# PM_Controller_v1p01.net
KiCad netlist of a schematic drawn in EAGLE
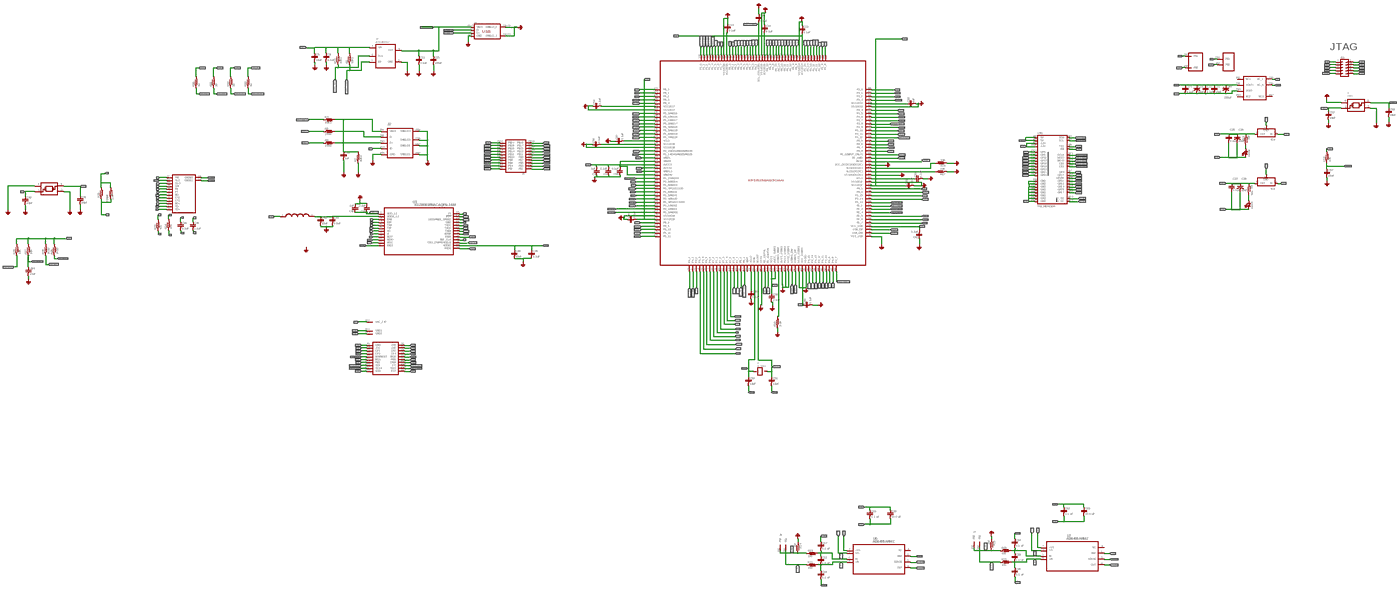
[diagram p0: schematic, sheet 1, overview]
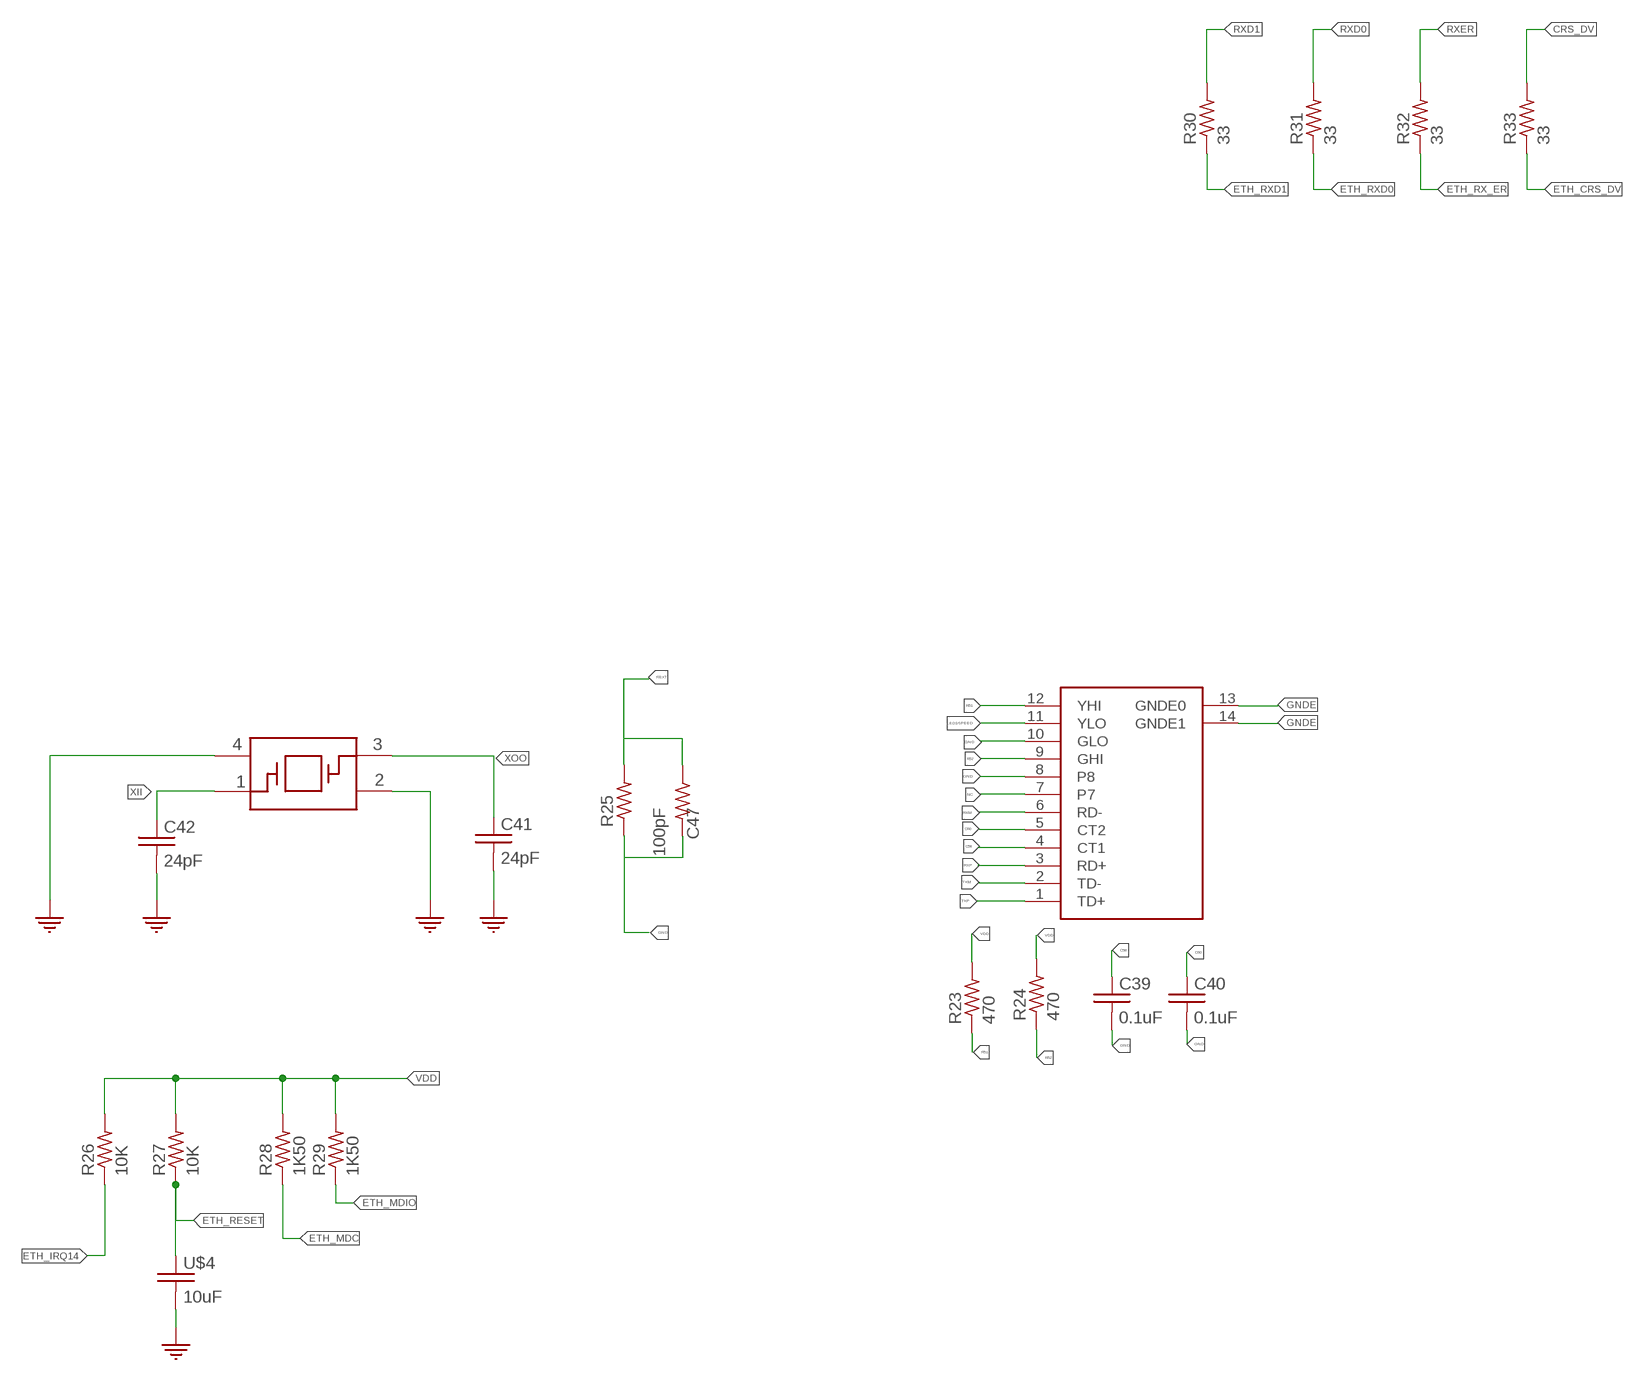
[diagram p1: schematic, sheet 1, part 1 of 6]
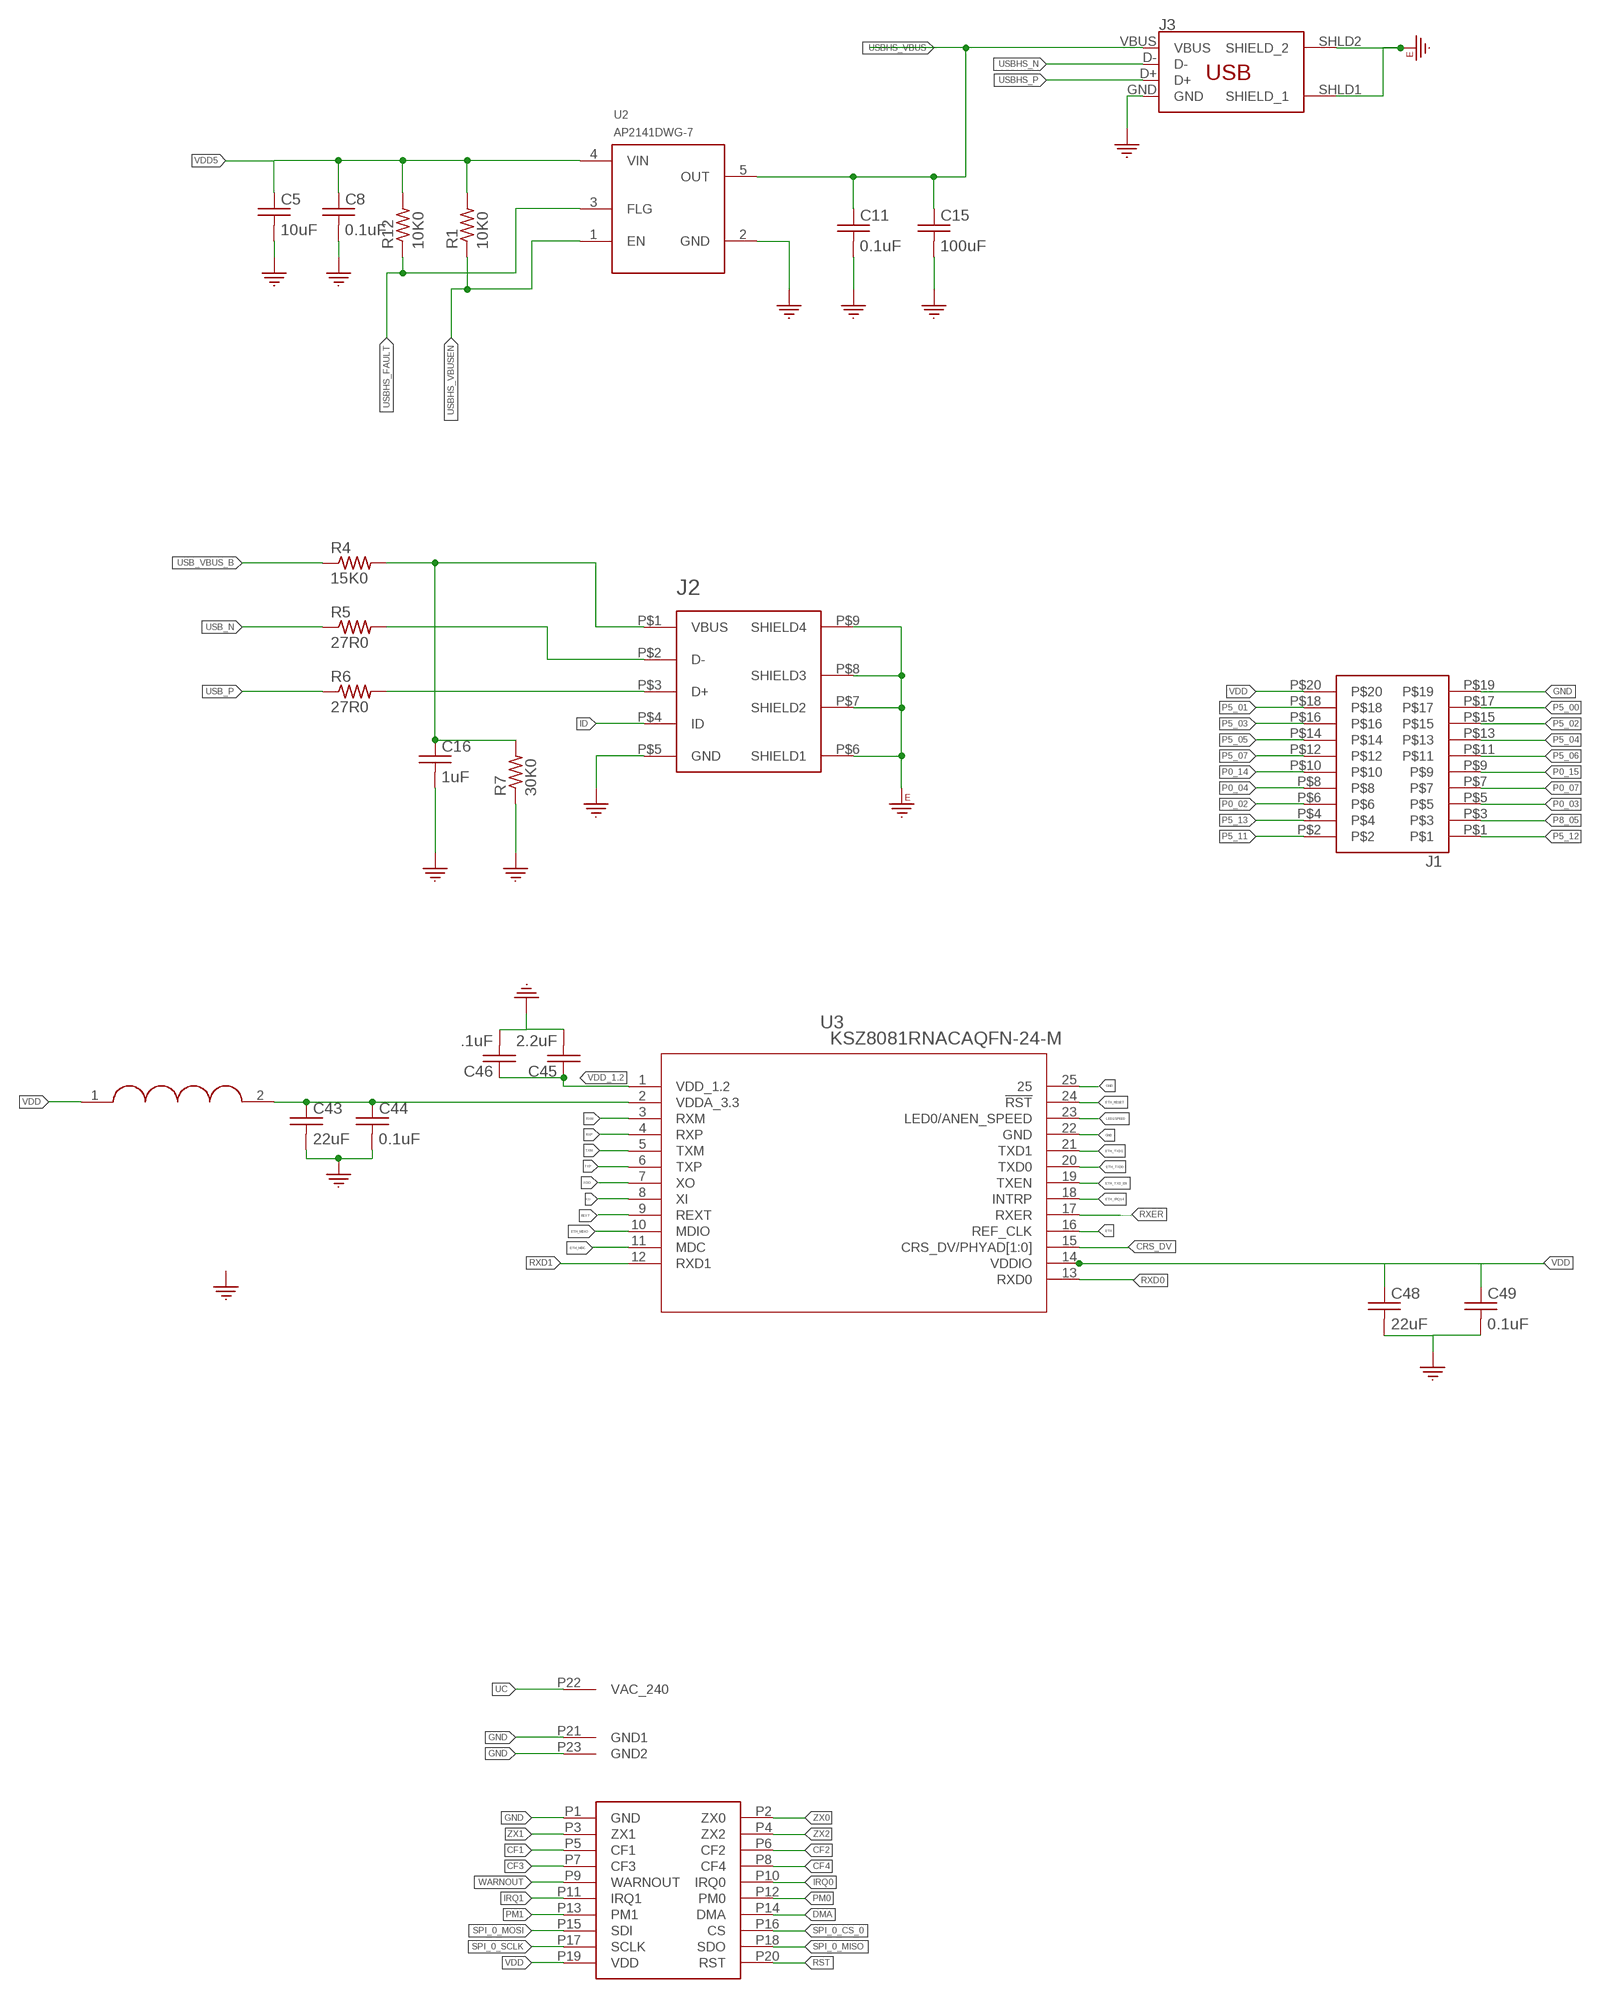
[diagram p2: schematic, sheet 1, part 2 of 6]
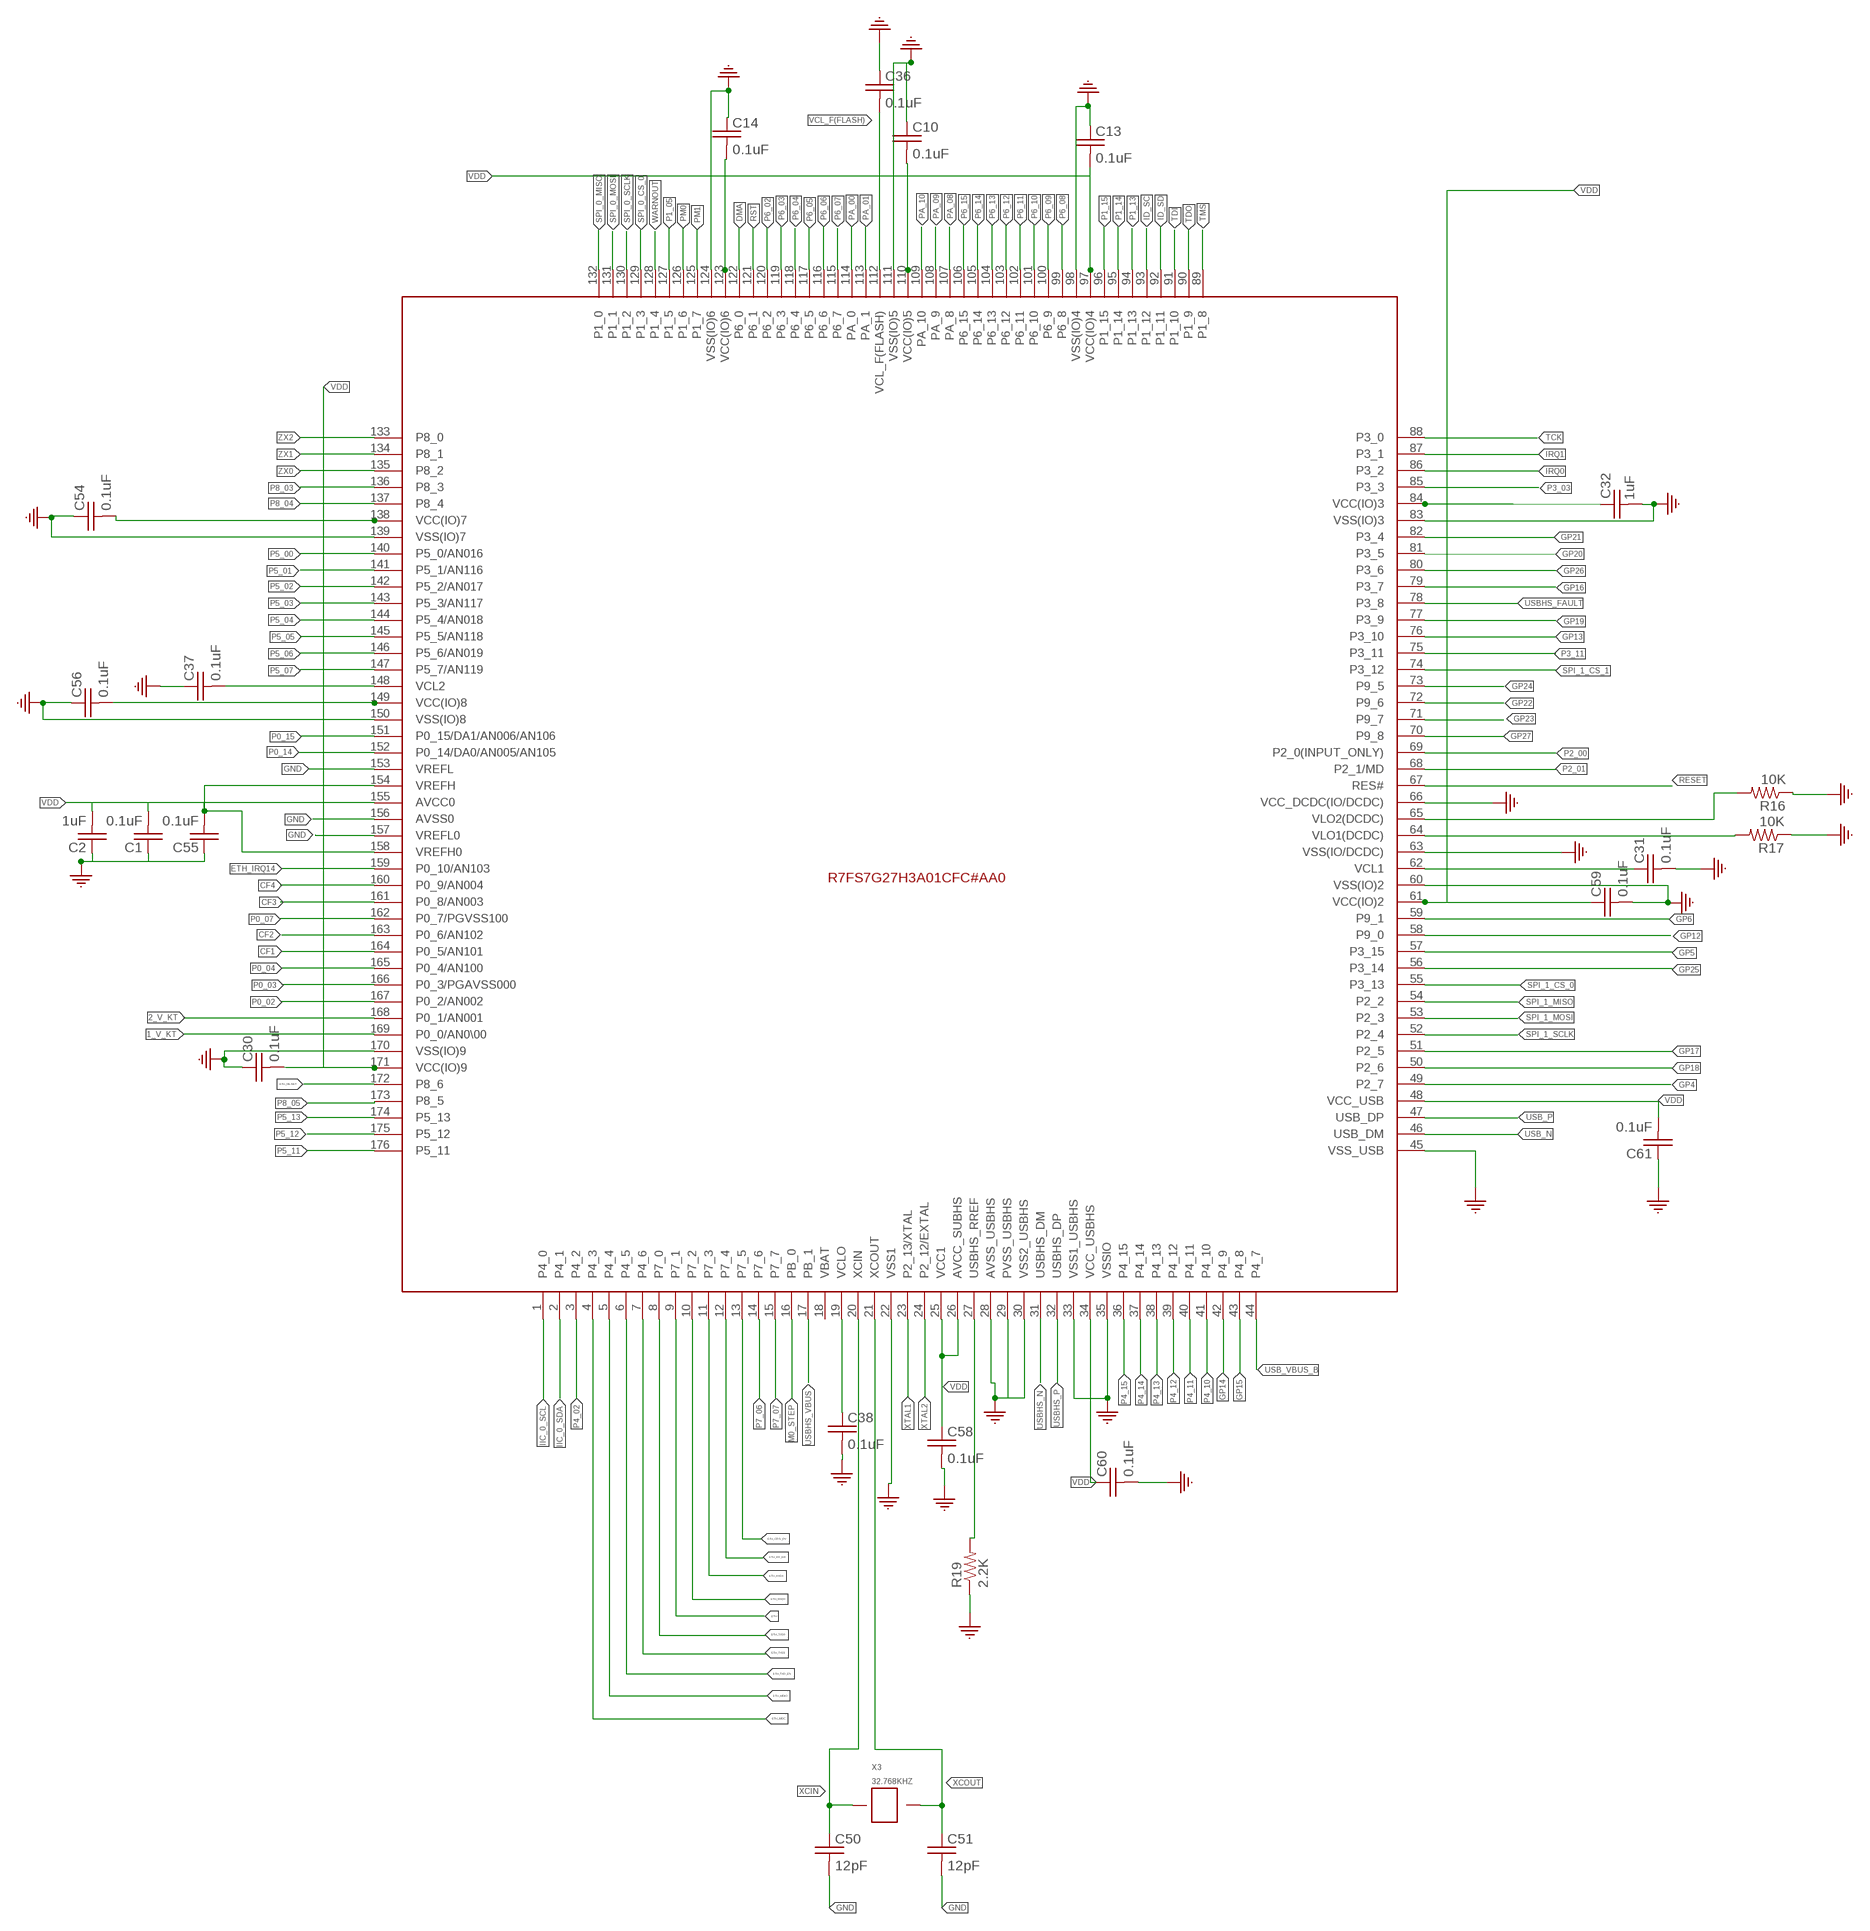
[diagram p3: schematic, sheet 1, part 3 of 6]
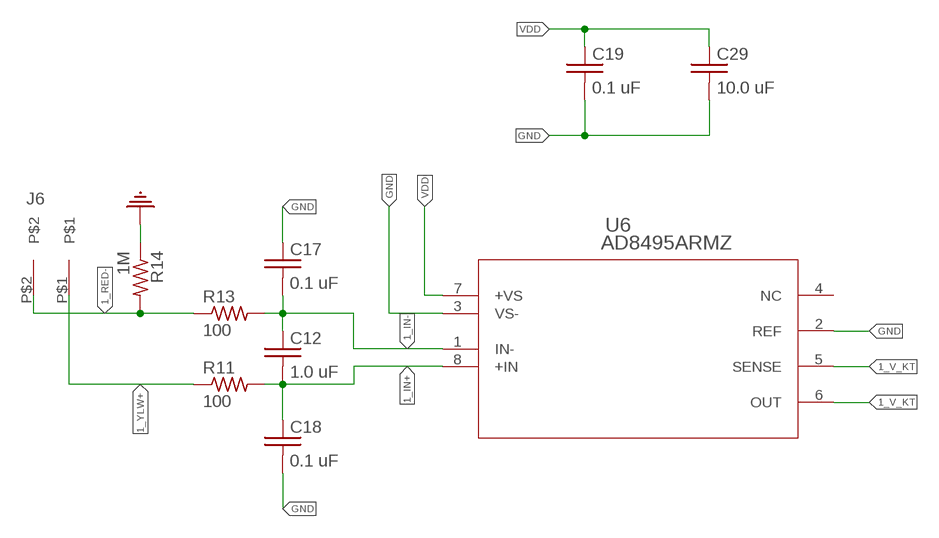
[diagram p4: schematic, sheet 1, part 4 of 6]
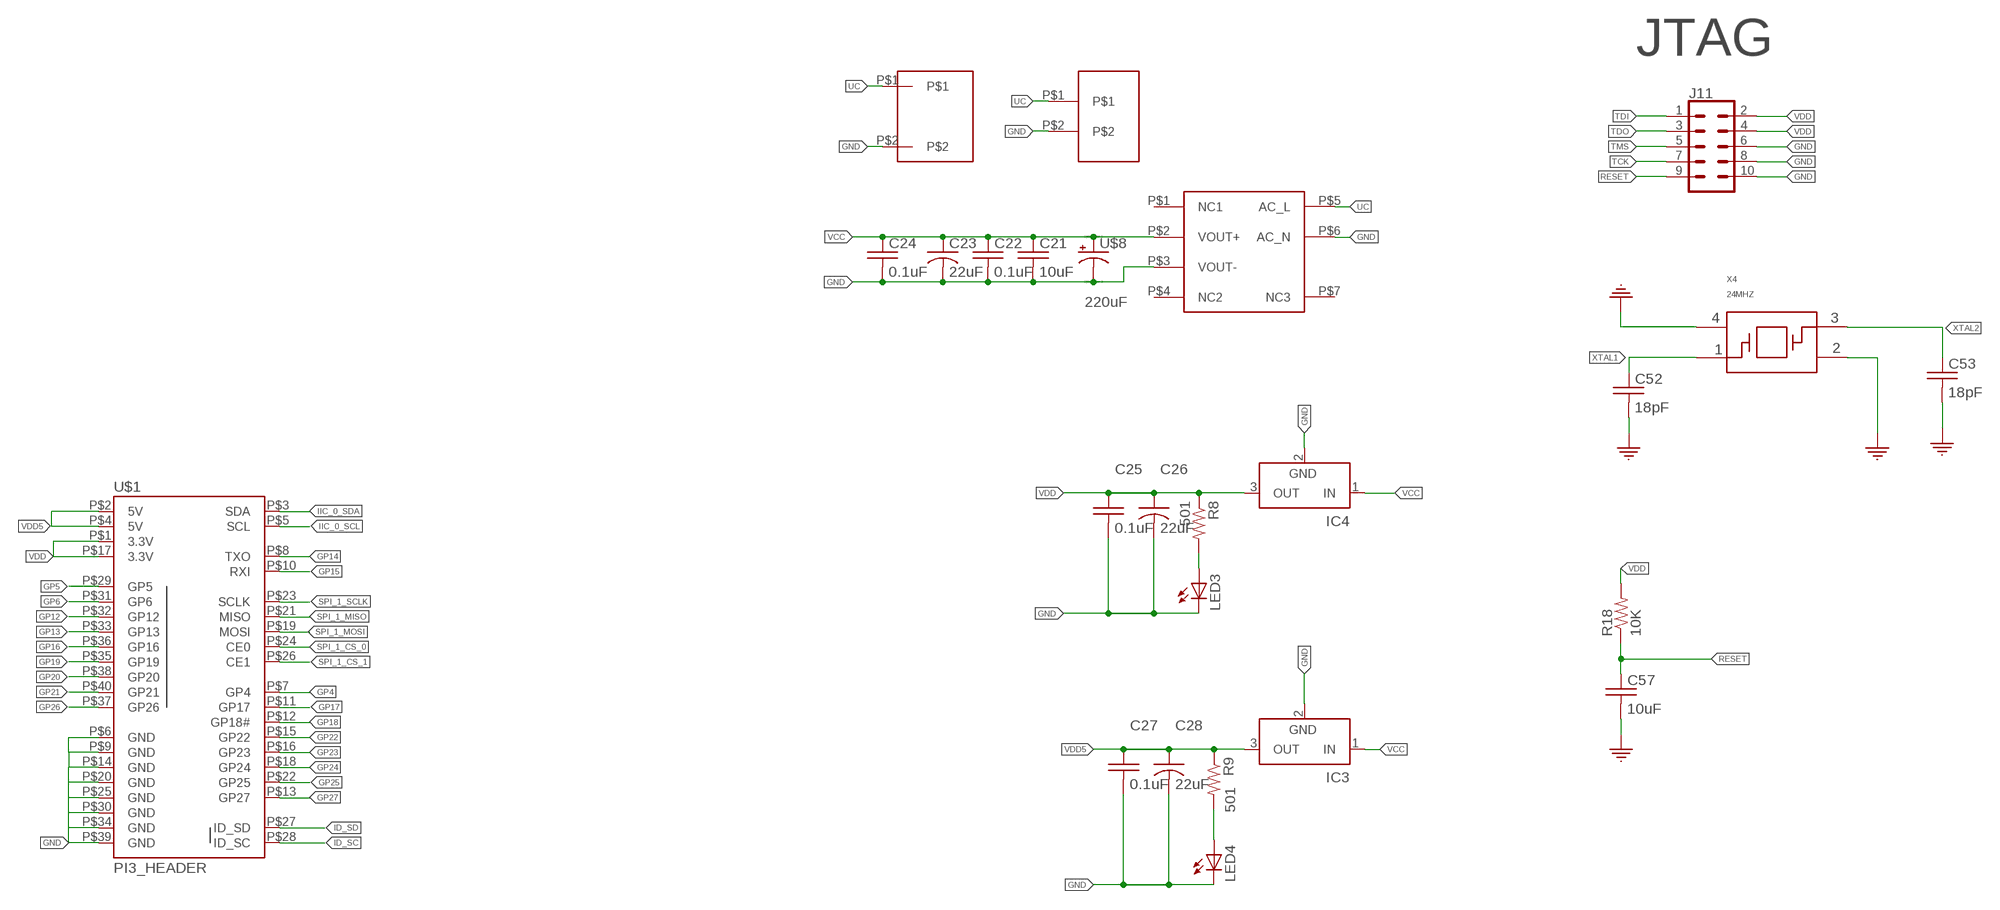
[diagram p5: schematic, sheet 1, part 5 of 6]
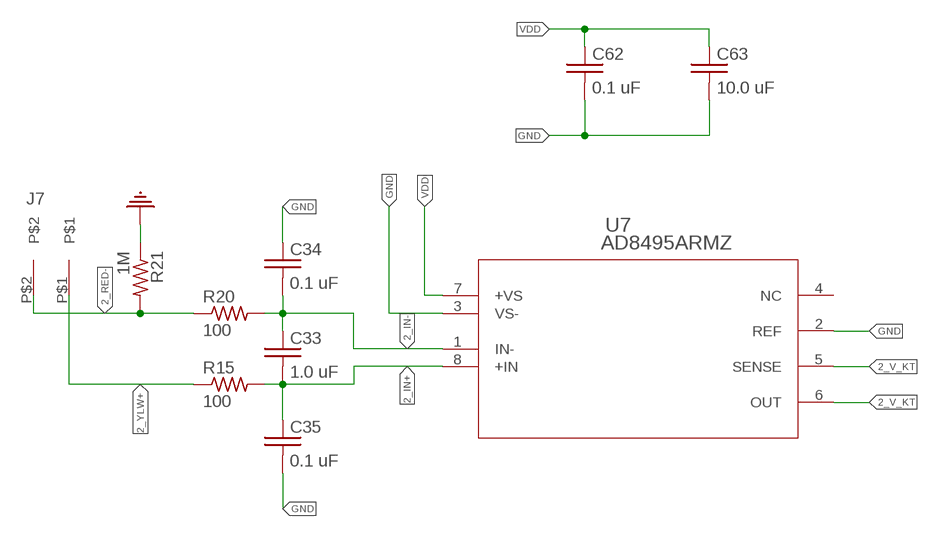
[diagram p6: schematic, sheet 1, part 6 of 6]

(export (version "E")
  (design (tool "Eeschema 10.0.6"))
  (components
    (comp (ref "C1")
      (value "0.1uF")
      (footprint "eagle-import:0402")
      (libsource (lib "eagle-import") (part "C_0402"))
    )
    (comp (ref "C2")
      (value "1uF")
      (footprint "eagle-import:0402")
      (libsource (lib "eagle-import") (part "C_0402"))
    )
    (comp (ref "C5")
      (value "10uF")
      (footprint "eagle-import:0402")
      (libsource (lib "eagle-import") (part "C_0402"))
    )
    (comp (ref "C8")
      (value "0.1uF")
      (footprint "eagle-import:0402")
      (libsource (lib "eagle-import") (part "C_0402"))
    )
    (comp (ref "C10")
      (value "0.1uF")
      (footprint "eagle-import:0402")
      (libsource (lib "eagle-import") (part "C_0402"))
    )
    (comp (ref "C11")
      (value "0.1uF")
      (footprint "eagle-import:0402")
      (libsource (lib "eagle-import") (part "C_0402"))
    )
    (comp (ref "C12")
      (value "1.0 uF")
      (footprint "eagle-import:0402")
      (libsource (lib "eagle-import") (part "C_0402"))
    )
    (comp (ref "C13")
      (value "0.1uF")
      (footprint "eagle-import:0402")
      (libsource (lib "eagle-import") (part "C_0402"))
    )
    (comp (ref "C14")
      (value "0.1uF")
      (footprint "eagle-import:0402")
      (libsource (lib "eagle-import") (part "C_0402"))
    )
    (comp (ref "C15")
      (value "100uF")
      (footprint "eagle-import:C1210")
      (libsource (lib "eagle-import") (part "C_1210"))
    )
    (comp (ref "C16")
      (value "1uF")
      (footprint "eagle-import:0402")
      (libsource (lib "eagle-import") (part "C_0402"))
    )
    (comp (ref "C17")
      (value "0.1 uF")
      (footprint "eagle-import:0402")
      (libsource (lib "eagle-import") (part "C_0402"))
    )
    (comp (ref "C18")
      (value "0.1 uF")
      (footprint "eagle-import:0402")
      (libsource (lib "eagle-import") (part "C_0402"))
    )
    (comp (ref "C19")
      (value "0.1 uF")
      (footprint "eagle-import:0402")
      (libsource (lib "eagle-import") (part "C_0402"))
    )
    (comp (ref "C20")
      (value "CAP_THIN_FILM_TDK_32922CAP")
      (footprint "eagle-import:CAP_THIN_FILM_32922")
      (libsource (lib "eagle-import") (part "CAP_THIN_FILM_TDK_32922CAP"))
    )
    (comp (ref "C21")
      (value "10uF")
      (footprint "eagle-import:0402")
      (libsource (lib "eagle-import") (part "C_0402"))
    )
    (comp (ref "C22")
      (value "0.1uF")
      (footprint "eagle-import:0402")
      (libsource (lib "eagle-import") (part "C_0402"))
    )
    (comp (ref "C23")
      (value "22uF")
      (footprint "eagle-import:C1206")
      (libsource (lib "eagle-import") (part "C-USC1206"))
    )
    (comp (ref "C24")
      (value "0.1uF")
      (footprint "eagle-import:0402")
      (libsource (lib "eagle-import") (part "C_0402"))
    )
    (comp (ref "C25")
      (value "0.1uF")
      (footprint "eagle-import:0402")
      (libsource (lib "eagle-import") (part "C_0402"))
    )
    (comp (ref "C26")
      (value "22uF")
      (footprint "eagle-import:C1206")
      (libsource (lib "eagle-import") (part "C-USC1206"))
    )
    (comp (ref "C27")
      (value "0.1uF")
      (footprint "eagle-import:0402")
      (libsource (lib "eagle-import") (part "C_0402"))
    )
    (comp (ref "C28")
      (value "22uF")
      (footprint "eagle-import:C1206")
      (libsource (lib "eagle-import") (part "C-USC1206"))
    )
    (comp (ref "C29")
      (value "10.0 uF")
      (footprint "eagle-import:0402")
      (libsource (lib "eagle-import") (part "C_0402"))
    )
    (comp (ref "C30")
      (value "0.1uF")
      (footprint "eagle-import:0402")
      (libsource (lib "eagle-import") (part "C_0402"))
    )
    (comp (ref "C31")
      (value "0.1uF")
      (footprint "eagle-import:0402")
      (libsource (lib "eagle-import") (part "C_0402"))
    )
    (comp (ref "C32")
      (value "1uF")
      (footprint "eagle-import:0402")
      (libsource (lib "eagle-import") (part "C_0402"))
    )
    (comp (ref "C33")
      (value "1.0 uF")
      (footprint "eagle-import:0402")
      (libsource (lib "eagle-import") (part "C_0402"))
    )
    (comp (ref "C34")
      (value "0.1 uF")
      (footprint "eagle-import:0402")
      (libsource (lib "eagle-import") (part "C_0402"))
    )
    (comp (ref "C35")
      (value "0.1 uF")
      (footprint "eagle-import:0402")
      (libsource (lib "eagle-import") (part "C_0402"))
    )
    (comp (ref "C36")
      (value "0.1uF")
      (footprint "eagle-import:0402")
      (libsource (lib "eagle-import") (part "C_0402"))
    )
    (comp (ref "C37")
      (value "0.1uF")
      (footprint "eagle-import:0402")
      (libsource (lib "eagle-import") (part "C_0402"))
    )
    (comp (ref "C38")
      (value "0.1uF")
      (footprint "eagle-import:0402")
      (libsource (lib "eagle-import") (part "C_0402"))
    )
    (comp (ref "C39")
      (value "0.1uF")
      (footprint "eagle-import:0402")
      (libsource (lib "eagle-import") (part "C_0402"))
    )
    (comp (ref "C40")
      (value "0.1uF")
      (footprint "eagle-import:0402")
      (libsource (lib "eagle-import") (part "C_0402"))
    )
    (comp (ref "C41")
      (value "24pF")
      (footprint "eagle-import:0402")
      (libsource (lib "eagle-import") (part "C_0402"))
    )
    (comp (ref "C42")
      (value "24pF")
      (footprint "eagle-import:0402")
      (libsource (lib "eagle-import") (part "C_0402"))
    )
    (comp (ref "C43")
      (value "22uF")
      (footprint "eagle-import:0603")
      (libsource (lib "eagle-import") (part "C_0603"))
    )
    (comp (ref "C44")
      (value "0.1uF")
      (footprint "eagle-import:0402")
      (libsource (lib "eagle-import") (part "C_0402"))
    )
    (comp (ref "C45")
      (value "2.2uF")
      (footprint "eagle-import:0402")
      (libsource (lib "eagle-import") (part "C_0402"))
    )
    (comp (ref "C46")
      (value ".1uF")
      (footprint "eagle-import:0402")
      (libsource (lib "eagle-import") (part "C_0402"))
    )
    (comp (ref "C47")
      (value "100pF")
      (footprint "eagle-import:0402")
      (libsource (lib "eagle-import") (part "R_0402"))
    )
    (comp (ref "C48")
      (value "22uF")
      (footprint "eagle-import:0603")
      (libsource (lib "eagle-import") (part "C_0603"))
    )
    (comp (ref "C49")
      (value "0.1uF")
      (footprint "eagle-import:0402")
      (libsource (lib "eagle-import") (part "C_0402"))
    )
    (comp (ref "C50")
      (value "12pF")
      (footprint "eagle-import:0402")
      (libsource (lib "eagle-import") (part "C_0402"))
    )
    (comp (ref "C51")
      (value "12pF")
      (footprint "eagle-import:0402")
      (libsource (lib "eagle-import") (part "C_0402"))
    )
    (comp (ref "C52")
      (value "18pF")
      (footprint "eagle-import:0402")
      (libsource (lib "eagle-import") (part "C_0402"))
    )
    (comp (ref "C53")
      (value "18pF")
      (footprint "eagle-import:0402")
      (libsource (lib "eagle-import") (part "C_0402"))
    )
    (comp (ref "C54")
      (value "0.1uF")
      (footprint "eagle-import:0402")
      (libsource (lib "eagle-import") (part "C_0402"))
    )
    (comp (ref "C55")
      (value "0.1uF")
      (footprint "eagle-import:0402")
      (libsource (lib "eagle-import") (part "C_0402"))
    )
    (comp (ref "C56")
      (value "0.1uF")
      (footprint "eagle-import:0402")
      (libsource (lib "eagle-import") (part "C_0402"))
    )
    (comp (ref "C57")
      (value "10uF")
      (footprint "eagle-import:0402")
      (libsource (lib "eagle-import") (part "C_0402"))
    )
    (comp (ref "C58")
      (value "0.1uF")
      (footprint "eagle-import:0402")
      (libsource (lib "eagle-import") (part "C_0402"))
    )
    (comp (ref "C59")
      (value "0.1uF")
      (footprint "eagle-import:0402")
      (libsource (lib "eagle-import") (part "C_0402"))
    )
    (comp (ref "C60")
      (value "0.1uF")
      (footprint "eagle-import:0402")
      (libsource (lib "eagle-import") (part "C_0402"))
    )
    (comp (ref "C61")
      (value "0.1uF")
      (footprint "eagle-import:0402")
      (libsource (lib "eagle-import") (part "C_0402"))
    )
    (comp (ref "C62")
      (value "0.1 uF")
      (footprint "eagle-import:0402")
      (libsource (lib "eagle-import") (part "C_0402"))
    )
    (comp (ref "C63")
      (value "10.0 uF")
      (footprint "eagle-import:0402")
      (libsource (lib "eagle-import") (part "C_0402"))
    )
    (comp (ref "FB2/2")
      (value "FB_0805_120_OHM")
      (footprint "eagle-import:0805")
      (libsource (lib "eagle-import") (part "FB_0805_120_OHM"))
    )
    (comp (ref "IC3")
      (value "LT1129CST5")
      (footprint "eagle-import:SOT223")
      (fields (field (name "MPN") "LT1129CST-5#PBF"))
      (libsource (lib "eagle-import") (part "LT1129CST5"))
    )
    (comp (ref "IC4")
      (value "LT1129CST3")
      (footprint "eagle-import:SOT223")
      (fields (field (name "MPN") "LT1129CST-5#PBF"))
      (libsource (lib "eagle-import") (part "LT1129CST3"))
    )
    (comp (ref "J1")
      (value "2_X_10_HEADER_GENERIC")
      (footprint "eagle-import:2_X_10_.1_INCH")
      (libsource (lib "eagle-import") (part "2_X_10_HEADER_GENERIC"))
    )
    (comp (ref "J2")
      (value "USB_MICRO-B")
      (footprint "eagle-import:USB_MICRO-B")
      (libsource (lib "eagle-import") (part "USB_MICRO-B"))
    )
    (comp (ref "J3")
      (value "USB_A")
      (footprint "eagle-import:USB_A_SMT")
      (libsource (lib "eagle-import") (part "USB_A"))
    )
    (comp (ref "J4")
      (value "RJ45_WITH_ELEC")
      (footprint "eagle-import:RJ45_TH_ELEC")
      (libsource (lib "eagle-import") (part "RJ45_WITH_ELEC"))
    )
    (comp (ref "J6")
      (value "3.81MM_1_X_2_RT_ANGLE_PLUG_HEADER")
      (footprint "eagle-import:2_3.81MM_PITCH")
      (libsource (lib "eagle-import") (part "3.81MM_1_X_2_RT_ANGLE_PLUG_HEADER"))
    )
    (comp (ref "J7")
      (value "3.81MM_1_X_2_RT_ANGLE_PLUG_HEADER")
      (footprint "eagle-import:2_3.81MM_PITCH")
      (libsource (lib "eagle-import") (part "3.81MM_1_X_2_RT_ANGLE_PLUG_HEADER"))
    )
    (comp (ref "J11")
      (value "CONN_05X2PTH")
      (footprint "eagle-import:2X5")
      (libsource (lib "eagle-import") (part "CONN_05X2PTH"))
    )
    (comp (ref "LED3")
      (value "LED_0805_GREEN")
      (footprint "eagle-import:LED_0805_GREEN")
      (libsource (lib "eagle-import") (part "LED_0805_GREEN"))
    )
    (comp (ref "LED4")
      (value "LED_0805_GREEN")
      (footprint "eagle-import:LED_0805_GREEN")
      (libsource (lib "eagle-import") (part "LED_0805_GREEN"))
    )
    (comp (ref "R1")
      (value "10K0")
      (footprint "eagle-import:0402")
      (libsource (lib "eagle-import") (part "R_0402"))
    )
    (comp (ref "R4")
      (value "15K0")
      (footprint "eagle-import:0402")
      (libsource (lib "eagle-import") (part "R_0402"))
    )
    (comp (ref "R5")
      (value "27R0")
      (footprint "eagle-import:0402")
      (libsource (lib "eagle-import") (part "R_0402"))
    )
    (comp (ref "R6")
      (value "27R0")
      (footprint "eagle-import:0402")
      (libsource (lib "eagle-import") (part "R_0402"))
    )
    (comp (ref "R7")
      (value "30K0")
      (footprint "eagle-import:0402")
      (libsource (lib "eagle-import") (part "R_0402"))
    )
    (comp (ref "R8")
      (value "501")
      (footprint "eagle-import:0402")
      (libsource (lib "eagle-import") (part "R_0402"))
    )
    (comp (ref "R9")
      (value "501")
      (footprint "eagle-import:0402")
      (libsource (lib "eagle-import") (part "R_0402"))
    )
    (comp (ref "R11")
      (value "100")
      (footprint "eagle-import:0402")
      (libsource (lib "eagle-import") (part "R_0402"))
    )
    (comp (ref "R12")
      (value "10K0")
      (footprint "eagle-import:0402")
      (libsource (lib "eagle-import") (part "R_0402"))
    )
    (comp (ref "R13")
      (value "100")
      (footprint "eagle-import:0402")
      (libsource (lib "eagle-import") (part "R_0402"))
    )
    (comp (ref "R14")
      (value "1M")
      (footprint "eagle-import:0402")
      (libsource (lib "eagle-import") (part "R_0402"))
    )
    (comp (ref "R15")
      (value "100")
      (footprint "eagle-import:0402")
      (libsource (lib "eagle-import") (part "R_0402"))
    )
    (comp (ref "R16")
      (value "10K")
      (footprint "eagle-import:0402")
      (libsource (lib "eagle-import") (part "R_0402"))
    )
    (comp (ref "R17")
      (value "10K")
      (footprint "eagle-import:0402")
      (libsource (lib "eagle-import") (part "R_0402"))
    )
    (comp (ref "R18")
      (value "10K")
      (footprint "eagle-import:0402")
      (libsource (lib "eagle-import") (part "R_0402"))
    )
    (comp (ref "R19")
      (value "2.2K")
      (footprint "eagle-import:0402")
      (libsource (lib "eagle-import") (part "R_0402"))
    )
    (comp (ref "R20")
      (value "100")
      (footprint "eagle-import:0402")
      (libsource (lib "eagle-import") (part "R_0402"))
    )
    (comp (ref "R21")
      (value "1M")
      (footprint "eagle-import:0402")
      (libsource (lib "eagle-import") (part "R_0402"))
    )
    (comp (ref "R23")
      (value "470")
      (footprint "eagle-import:0402")
      (libsource (lib "eagle-import") (part "R_0402"))
    )
    (comp (ref "R24")
      (value "470")
      (footprint "eagle-import:0402")
      (libsource (lib "eagle-import") (part "R_0402"))
    )
    (comp (ref "R25")
      (value "6k49")
      (footprint "eagle-import:0402")
      (libsource (lib "eagle-import") (part "R_0402"))
    )
    (comp (ref "R26")
      (value "10K")
      (footprint "eagle-import:0402")
      (libsource (lib "eagle-import") (part "R_0402"))
    )
    (comp (ref "R27")
      (value "10K")
      (footprint "eagle-import:0402")
      (libsource (lib "eagle-import") (part "R_0402"))
    )
    (comp (ref "R28")
      (value "1K50")
      (footprint "eagle-import:0402")
      (libsource (lib "eagle-import") (part "R_0402"))
    )
    (comp (ref "R29")
      (value "1K50")
      (footprint "eagle-import:0402")
      (libsource (lib "eagle-import") (part "R_0402"))
    )
    (comp (ref "R30")
      (value "33")
      (footprint "eagle-import:0402")
      (libsource (lib "eagle-import") (part "R_0402"))
    )
    (comp (ref "R31")
      (value "33")
      (footprint "eagle-import:0402")
      (libsource (lib "eagle-import") (part "R_0402"))
    )
    (comp (ref "R32")
      (value "33")
      (footprint "eagle-import:0402")
      (libsource (lib "eagle-import") (part "R_0402"))
    )
    (comp (ref "R33")
      (value "33")
      (footprint "eagle-import:0402")
      (libsource (lib "eagle-import") (part "R_0402"))
    )
    (comp (ref "U$1")
      (value "PI3_HEADER")
      (footprint "eagle-import:HEADER_2_X_20_.1_INCH")
      (libsource (lib "eagle-import") (part "PI3_HEADER"))
    )
    (comp (ref "U$2")
      (value "METER_BASE")
      (footprint "eagle-import:METER_BASE")
      (libsource (lib "eagle-import") (part "METER_BASE"))
    )
    (comp (ref "U$3")
      (value "XTAL_25_MHZ")
      (footprint "eagle-import:SMD_3225")
      (libsource (lib "eagle-import") (part "XTAL_25_MHZ"))
    )
    (comp (ref "U$4")
      (value "10uF")
      (footprint "eagle-import:0402")
      (libsource (lib "eagle-import") (part "C_0402"))
    )
    (comp (ref "U$7")
      (value "VAR_10MM_VDRUS10")
      (footprint "eagle-import:VAR_10MM_VDRUS10")
      (libsource (lib "eagle-import") (part "VAR_10MM_VDRUS10"))
    )
    (comp (ref "U$8")
      (value "220uF")
      (footprint "eagle-import:C_AL_ELECTROLYTIC_SMD_220UF")
      (libsource (lib "eagle-import") (part "C_AL_ELECTROLYTIC_SMD_220UF"))
    )
    (comp (ref "U2")
      (value "AP2141DWG-5")
      (footprint "eagle-import:SOT-23-5")
      (libsource (lib "eagle-import") (part "AP2141DWG-5"))
    )
    (comp (ref "U3")
      (value "KSZ8081RNACAQFN-24-M")
      (footprint "eagle-import:QFN-24-M")
      (fields (field (name "MANUFACTURER_PART_NUMBER") "KSZ8081RNACA"))
      (libsource (lib "eagle-import") (part "KSZ8081RNACAQFN-24-M"))
    )
    (comp (ref "U4")
      (value "S7G2_X_176")
      (footprint "eagle-import:LQFP176_24X24")
      (libsource (lib "eagle-import") (part "S7G2_X_176"))
    )
    (comp (ref "U5")
      (value "TMLM_04109")
      (footprint "eagle-import:TMLM04")
      (libsource (lib "eagle-import") (part "TMLM_04109"))
    )
    (comp (ref "U6")
      (value "AD8495ARMZ")
      (footprint "eagle-import:RM_8_ADI")
      (libsource (lib "eagle-import") (part "AD8495ARMZ"))
    )
    (comp (ref "U7")
      (value "AD8495ARMZ")
      (footprint "eagle-import:RM_8_ADI")
      (libsource (lib "eagle-import") (part "AD8495ARMZ"))
    )
    (comp (ref "X3")
      (value "32.768KHZ")
      (footprint "eagle-import:SMD_X_2_PADS")
      (libsource (lib "eagle-import") (part "XTAL_32.768KHZ"))
    )
    (comp (ref "X4")
      (value "24MHZ")
      (footprint "eagle-import:SMD_3225")
      (libsource (lib "eagle-import") (part "XTAL_24_MHZ"))
    )
  )
  (nets
    (net (code "1") (name "1_IN+") (class "Default")
      (node (ref "C12") (pin "P$2") (pinfunction "2_P$2") (pintype "passive"))
      (node (ref "C18") (pin "P$1") (pinfunction "1_P$1") (pintype "passive"))
      (node (ref "R11") (pin "P$2") (pinfunction "2_P$2") (pintype "passive"))
      (node (ref "U6") (pin "8") (pinfunction "+IN_8") (pintype "input"))
    )
    (net (code "2") (name "1_IN-") (class "Default")
      (node (ref "C12") (pin "P$1") (pinfunction "1_P$1") (pintype "passive"))
      (node (ref "C17") (pin "P$2") (pinfunction "2_P$2") (pintype "passive"))
      (node (ref "R13") (pin "P$2") (pinfunction "2_P$2") (pintype "passive"))
      (node (ref "U6") (pin "1") (pinfunction "IN-_1") (pintype "input"))
    )
    (net (code "3") (name "1_RED-") (class "Default")
      (node (ref "J6") (pin "P$2") (pinfunction "P$2_P$2") (pintype "bidirectional"))
      (node (ref "R13") (pin "P$1") (pinfunction "1_P$1") (pintype "passive"))
      (node (ref "R14") (pin "P$2") (pinfunction "2_P$2") (pintype "passive"))
    )
    (net (code "4") (name "1_V_KT") (class "Default")
      (node (ref "U4") (pin "169") (pinfunction "P0_0/AN0\\00_169") (pintype "bidirectional"))
      (node (ref "U6") (pin "5") (pinfunction "SENSE_5") (pintype "passive"))
      (node (ref "U6") (pin "6") (pinfunction "OUT_6") (pintype "output"))
    )
    (net (code "5") (name "1_YLW+") (class "Default")
      (node (ref "J6") (pin "P$1") (pinfunction "P$1_P$1") (pintype "bidirectional"))
      (node (ref "R11") (pin "P$1") (pinfunction "1_P$1") (pintype "passive"))
    )
    (net (code "6") (name "2_IN+") (class "Default")
      (node (ref "C33") (pin "P$2") (pinfunction "2_P$2") (pintype "passive"))
      (node (ref "C35") (pin "P$1") (pinfunction "1_P$1") (pintype "passive"))
      (node (ref "R15") (pin "P$2") (pinfunction "2_P$2") (pintype "passive"))
      (node (ref "U7") (pin "8") (pinfunction "+IN_8") (pintype "input"))
    )
    (net (code "7") (name "2_IN-") (class "Default")
      (node (ref "C33") (pin "P$1") (pinfunction "1_P$1") (pintype "passive"))
      (node (ref "C34") (pin "P$2") (pinfunction "2_P$2") (pintype "passive"))
      (node (ref "R20") (pin "P$2") (pinfunction "2_P$2") (pintype "passive"))
      (node (ref "U7") (pin "1") (pinfunction "IN-_1") (pintype "input"))
    )
    (net (code "8") (name "2_RED-") (class "Default")
      (node (ref "J7") (pin "P$2") (pinfunction "P$2_P$2") (pintype "bidirectional"))
      (node (ref "R20") (pin "P$1") (pinfunction "1_P$1") (pintype "passive"))
      (node (ref "R21") (pin "P$2") (pinfunction "2_P$2") (pintype "passive"))
    )
    (net (code "9") (name "2_V_KT") (class "Default")
      (node (ref "U4") (pin "168") (pinfunction "P0_1/AN001_168") (pintype "bidirectional"))
      (node (ref "U7") (pin "5") (pinfunction "SENSE_5") (pintype "passive"))
      (node (ref "U7") (pin "6") (pinfunction "OUT_6") (pintype "output"))
    )
    (net (code "10") (name "2_YLW+") (class "Default")
      (node (ref "J7") (pin "P$1") (pinfunction "P$1_P$1") (pintype "bidirectional"))
      (node (ref "R15") (pin "P$1") (pinfunction "1_P$1") (pintype "passive"))
    )
    (net (code "11") (name "C58") (class "Default")
      (node (ref "C39") (pin "P$1") (pinfunction "1_P$1") (pintype "passive"))
      (node (ref "J4") (pin "4") (pinfunction "CT1_4") (pintype "bidirectional"))
    )
    (net (code "12") (name "C60") (class "Default")
      (node (ref "C40") (pin "P$1") (pinfunction "1_P$1") (pintype "passive"))
      (node (ref "J4") (pin "5") (pinfunction "CT2_5") (pintype "bidirectional"))
    )
    (net (code "13") (name "CF1") (class "Default")
      (node (ref "U$2") (pin "P5") (pinfunction "CF1_P5") (pintype "bidirectional"))
      (node (ref "U4") (pin "164") (pinfunction "P0_5/AN101_164") (pintype "bidirectional"))
    )
    (net (code "14") (name "CF2") (class "Default")
      (node (ref "U$2") (pin "P6") (pinfunction "CF2_P6") (pintype "bidirectional"))
      (node (ref "U4") (pin "163") (pinfunction "P0_6/AN102_163") (pintype "bidirectional"))
    )
    (net (code "15") (name "CF3") (class "Default")
      (node (ref "U$2") (pin "P7") (pinfunction "CF3_P7") (pintype "bidirectional"))
      (node (ref "U4") (pin "161") (pinfunction "P0_8/AN003_161") (pintype "bidirectional"))
    )
    (net (code "16") (name "CF4") (class "Default")
      (node (ref "U$2") (pin "P8") (pinfunction "CF4_P8") (pintype "bidirectional"))
      (node (ref "U4") (pin "160") (pinfunction "P0_9/AN004_160") (pintype "bidirectional"))
    )
    (net (code "17") (name "CRS_DV") (class "Default")
      (node (ref "R33") (pin "P$2") (pinfunction "2_P$2") (pintype "passive"))
      (node (ref "U3") (pin "15") (pinfunction "CRS_DV/PHYAD[1:0]_15") (pintype "bidirectional"))
    )
    (net (code "18") (name "DMA") (class "Default")
      (node (ref "U$2") (pin "P14") (pinfunction "DMA_P14") (pintype "bidirectional"))
      (node (ref "U4") (pin "122") (pinfunction "P6_0_122") (pintype "bidirectional"))
    )
    (net (code "19") (name "ETH") (class "Default")
      (node (ref "U3") (pin "16") (pinfunction "REF_CLK_16") (pintype "bidirectional"))
      (node (ref "U4") (pin "9") (pinfunction "P7_1_9") (pintype "bidirectional"))
    )
    (net (code "20") (name "ETH_CRS_DV") (class "Default")
      (node (ref "R33") (pin "P$1") (pinfunction "1_P$1") (pintype "passive"))
      (node (ref "U4") (pin "13") (pinfunction "P7_5_13") (pintype "bidirectional"))
    )
    (net (code "21") (name "ETH_IRQ14") (class "Default")
      (node (ref "R26") (pin "P$1") (pinfunction "1_P$1") (pintype "passive"))
      (node (ref "U3") (pin "18") (pinfunction "INTRP_18") (pintype "bidirectional"))
      (node (ref "U4") (pin "159") (pinfunction "P0_10/AN103_159") (pintype "bidirectional"))
    )
    (net (code "22") (name "ETH_MDC") (class "Default")
      (node (ref "R28") (pin "P$1") (pinfunction "1_P$1") (pintype "passive"))
      (node (ref "U3") (pin "11") (pinfunction "MDC_11") (pintype "input"))
      (node (ref "U4") (pin "4") (pinfunction "P4_3_4") (pintype "bidirectional"))
    )
    (net (code "23") (name "ETH_MDIO") (class "Default")
      (node (ref "R29") (pin "P$1") (pinfunction "1_P$1") (pintype "passive"))
      (node (ref "U3") (pin "10") (pinfunction "MDIO_10") (pintype "bidirectional"))
      (node (ref "U4") (pin "5") (pinfunction "P4_4_5") (pintype "bidirectional"))
    )
    (net (code "24") (name "ETH_RESET") (class "Default")
      (node (ref "R27") (pin "P$1") (pinfunction "1_P$1") (pintype "passive"))
      (node (ref "U$4") (pin "P$1") (pinfunction "1_P$1") (pintype "passive"))
      (node (ref "U3") (pin "24") (pinfunction "~{RST}_24") (pintype "input"))
      (node (ref "U4") (pin "172") (pinfunction "P8_6_172") (pintype "bidirectional"))
    )
    (net (code "25") (name "ETH_RXD0") (class "Default")
      (node (ref "R31") (pin "P$1") (pinfunction "1_P$1") (pintype "passive"))
      (node (ref "U4") (pin "10") (pinfunction "P7_2_10") (pintype "bidirectional"))
    )
    (net (code "26") (name "ETH_RXD1") (class "Default")
      (node (ref "R30") (pin "P$1") (pinfunction "1_P$1") (pintype "passive"))
      (node (ref "U4") (pin "11") (pinfunction "P7_3_11") (pintype "bidirectional"))
    )
    (net (code "27") (name "ETH_RX_ER") (class "Default")
      (node (ref "R32") (pin "P$1") (pinfunction "1_P$1") (pintype "passive"))
      (node (ref "U4") (pin "12") (pinfunction "P7_4_12") (pintype "bidirectional"))
    )
    (net (code "28") (name "ETH_TXD0") (class "Default")
      (node (ref "U3") (pin "20") (pinfunction "TXD0_20") (pintype "input"))
      (node (ref "U4") (pin "8") (pinfunction "P7_0_8") (pintype "bidirectional"))
    )
    (net (code "29") (name "ETH_TXD1") (class "Default")
      (node (ref "U3") (pin "21") (pinfunction "TXD1_21") (pintype "bidirectional"))
      (node (ref "U4") (pin "7") (pinfunction "P4_6_7") (pintype "bidirectional"))
    )
    (net (code "30") (name "ETH_TXD_EN") (class "Default")
      (node (ref "U3") (pin "19") (pinfunction "TXEN_19") (pintype "input"))
      (node (ref "U4") (pin "6") (pinfunction "P4_5_6") (pintype "bidirectional"))
    )
    (net (code "31") (name "GND") (class "Default")
      (node (ref "C1") (pin "P$1") (pinfunction "1_P$1") (pintype "passive"))
      (node (ref "C10") (pin "P$1") (pinfunction "1_P$1") (pintype "passive"))
      (node (ref "C11") (pin "P$2") (pinfunction "2_P$2") (pintype "passive"))
      (node (ref "C13") (pin "P$1") (pinfunction "1_P$1") (pintype "passive"))
      (node (ref "C14") (pin "P$1") (pinfunction "1_P$1") (pintype "passive"))
      (node (ref "C15") (pin "2") (pinfunction "2_2") (pintype "passive"))
      (node (ref "C16") (pin "P$2") (pinfunction "2_P$2") (pintype "passive"))
      (node (ref "C17") (pin "P$1") (pinfunction "1_P$1") (pintype "passive"))
      (node (ref "C18") (pin "P$2") (pinfunction "2_P$2") (pintype "passive"))
      (node (ref "C19") (pin "P$2") (pinfunction "2_P$2") (pintype "passive"))
      (node (ref "C2") (pin "P$1") (pinfunction "1_P$1") (pintype "passive"))
      (node (ref "C20") (pin "P$2") (pinfunction "P$2_P$2") (pintype "bidirectional"))
      (node (ref "C21") (pin "P$2") (pinfunction "2_P$2") (pintype "passive"))
      (node (ref "C22") (pin "P$2") (pinfunction "2_P$2") (pintype "passive"))
      (node (ref "C23") (pin "2") (pinfunction "2_2") (pintype "passive"))
      (node (ref "C24") (pin "P$2") (pinfunction "2_P$2") (pintype "passive"))
      (node (ref "C25") (pin "P$2") (pinfunction "2_P$2") (pintype "passive"))
      (node (ref "C26") (pin "2") (pinfunction "2_2") (pintype "passive"))
      (node (ref "C27") (pin "P$2") (pinfunction "2_P$2") (pintype "passive"))
      (node (ref "C28") (pin "2") (pinfunction "2_2") (pintype "passive"))
      (node (ref "C29") (pin "P$2") (pinfunction "2_P$2") (pintype "passive"))
      (node (ref "C30") (pin "P$1") (pinfunction "1_P$1") (pintype "passive"))
      (node (ref "C31") (pin "P$2") (pinfunction "2_P$2") (pintype "passive"))
      (node (ref "C32") (pin "P$2") (pinfunction "2_P$2") (pintype "passive"))
      (node (ref "C34") (pin "P$1") (pinfunction "1_P$1") (pintype "passive"))
      (node (ref "C35") (pin "P$2") (pinfunction "2_P$2") (pintype "passive"))
      (node (ref "C36") (pin "P$1") (pinfunction "1_P$1") (pintype "passive"))
      (node (ref "C37") (pin "P$1") (pinfunction "1_P$1") (pintype "passive"))
      (node (ref "C38") (pin "P$2") (pinfunction "2_P$2") (pintype "passive"))
      (node (ref "C39") (pin "P$2") (pinfunction "2_P$2") (pintype "passive"))
      (node (ref "C40") (pin "P$2") (pinfunction "2_P$2") (pintype "passive"))
      (node (ref "C41") (pin "P$2") (pinfunction "2_P$2") (pintype "passive"))
      (node (ref "C42") (pin "P$2") (pinfunction "2_P$2") (pintype "passive"))
      (node (ref "C43") (pin "2") (pinfunction "2_2") (pintype "passive"))
      (node (ref "C44") (pin "P$2") (pinfunction "2_P$2") (pintype "passive"))
      (node (ref "C45") (pin "P$2") (pinfunction "2_P$2") (pintype "passive"))
      (node (ref "C46") (pin "P$2") (pinfunction "2_P$2") (pintype "passive"))
      (node (ref "C47") (pin "P$2") (pinfunction "2_P$2") (pintype "passive"))
      (node (ref "C48") (pin "2") (pinfunction "2_2") (pintype "passive"))
      (node (ref "C49") (pin "P$2") (pinfunction "2_P$2") (pintype "passive"))
      (node (ref "C5") (pin "P$2") (pinfunction "2_P$2") (pintype "passive"))
      (node (ref "C50") (pin "P$2") (pinfunction "2_P$2") (pintype "passive"))
      (node (ref "C51") (pin "P$2") (pinfunction "2_P$2") (pintype "passive"))
      (node (ref "C52") (pin "P$2") (pinfunction "2_P$2") (pintype "passive"))
      (node (ref "C53") (pin "P$2") (pinfunction "2_P$2") (pintype "passive"))
      (node (ref "C54") (pin "P$1") (pinfunction "1_P$1") (pintype "passive"))
      (node (ref "C55") (pin "P$1") (pinfunction "1_P$1") (pintype "passive"))
      (node (ref "C56") (pin "P$1") (pinfunction "1_P$1") (pintype "passive"))
      (node (ref "C57") (pin "P$2") (pinfunction "2_P$2") (pintype "passive"))
      (node (ref "C58") (pin "P$2") (pinfunction "2_P$2") (pintype "passive"))
      (node (ref "C59") (pin "P$2") (pinfunction "2_P$2") (pintype "passive"))
      (node (ref "C60") (pin "P$2") (pinfunction "2_P$2") (pintype "passive"))
      (node (ref "C61") (pin "P$1") (pinfunction "1_P$1") (pintype "passive"))
      (node (ref "C62") (pin "P$2") (pinfunction "2_P$2") (pintype "passive"))
      (node (ref "C63") (pin "P$2") (pinfunction "2_P$2") (pintype "passive"))
      (node (ref "C8") (pin "P$2") (pinfunction "2_P$2") (pintype "passive"))
      (node (ref "IC3") (pin "2") (pinfunction "GND_2") (pintype "power_in"))
      (node (ref "IC4") (pin "2") (pinfunction "GND_2") (pintype "power_in"))
      (node (ref "J1") (pin "P$19") (pinfunction "P$19_P$19") (pintype "bidirectional"))
      (node (ref "J11") (pin "10") (pinfunction "10_10") (pintype "passive"))
      (node (ref "J11") (pin "6") (pinfunction "6_6") (pintype "passive"))
      (node (ref "J11") (pin "8") (pinfunction "8_8") (pintype "passive"))
      (node (ref "J2") (pin "P$5") (pinfunction "GND_P$5") (pintype "bidirectional"))
      (node (ref "J3") (pin "GND") (pinfunction "GND_GND") (pintype "power_in"))
      (node (ref "J4") (pin "10") (pinfunction "GLO_10") (pintype "bidirectional"))
      (node (ref "J4") (pin "8") (pinfunction "P8_8") (pintype "bidirectional"))
      (node (ref "LED3") (pin "C") (pinfunction "C_C") (pintype "passive"))
      (node (ref "LED4") (pin "C") (pinfunction "C_C") (pintype "passive"))
      (node (ref "R14") (pin "P$1") (pinfunction "1_P$1") (pintype "passive"))
      (node (ref "R16") (pin "P$1") (pinfunction "1_P$1") (pintype "passive"))
      (node (ref "R17") (pin "P$1") (pinfunction "1_P$1") (pintype "passive"))
      (node (ref "R19") (pin "P$1") (pinfunction "1_P$1") (pintype "passive"))
      (node (ref "R21") (pin "P$1") (pinfunction "1_P$1") (pintype "passive"))
      (node (ref "R25") (pin "P$1") (pinfunction "1_P$1") (pintype "passive"))
      (node (ref "R7") (pin "P$1") (pinfunction "1_P$1") (pintype "passive"))
      (node (ref "U$1") (pin "P$14") (pinfunction "GND_P$14") (pintype "power_in"))
      (node (ref "U$1") (pin "P$20") (pinfunction "GND_P$20") (pintype "power_in"))
      (node (ref "U$1") (pin "P$25") (pinfunction "GND_P$25") (pintype "power_in"))
      (node (ref "U$1") (pin "P$30") (pinfunction "GND_P$30") (pintype "power_in"))
      (node (ref "U$1") (pin "P$34") (pinfunction "GND_P$34") (pintype "power_in"))
      (node (ref "U$1") (pin "P$39") (pinfunction "GND_P$39") (pintype "power_in"))
      (node (ref "U$1") (pin "P$6") (pinfunction "GND_P$6") (pintype "power_in"))
      (node (ref "U$1") (pin "P$9") (pinfunction "GND_P$9") (pintype "power_in"))
      (node (ref "U$2") (pin "P1") (pinfunction "GND_P1") (pintype "bidirectional"))
      (node (ref "U$2") (pin "P21") (pinfunction "GND1_P21") (pintype "bidirectional"))
      (node (ref "U$2") (pin "P23") (pinfunction "GND2_P23") (pintype "bidirectional"))
      (node (ref "U$3") (pin "2") (pinfunction "2_2") (pintype "bidirectional"))
      (node (ref "U$3") (pin "4") (pinfunction "4_4") (pintype "bidirectional"))
      (node (ref "U$4") (pin "P$2") (pinfunction "2_P$2") (pintype "passive"))
      (node (ref "U$7") (pin "P$2") (pinfunction "P$2_P$2") (pintype "bidirectional"))
      (node (ref "U$8") (pin "N-") (pinfunction "-_N-") (pintype "passive"))
      (node (ref "U2") (pin "2") (pinfunction "GND_2") (pintype "input"))
      (node (ref "U3") (pin "22") (pinfunction "GND_22") (pintype "power_in"))
      (node (ref "U3") (pin "25") (pinfunction "25_25") (pintype "passive"))
      (node (ref "U4") (pin "111") (pinfunction "VSS(IO)5_111") (pintype "bidirectional"))
      (node (ref "U4") (pin "124") (pinfunction "VSS(IO)6_124") (pintype "bidirectional"))
      (node (ref "U4") (pin "139") (pinfunction "VSS(IO)7_139") (pintype "bidirectional"))
      (node (ref "U4") (pin "150") (pinfunction "VSS(IO)8_150") (pintype "bidirectional"))
      (node (ref "U4") (pin "153") (pinfunction "VREFL_153") (pintype "bidirectional"))
      (node (ref "U4") (pin "156") (pinfunction "AVSS0_156") (pintype "bidirectional"))
      (node (ref "U4") (pin "157") (pinfunction "VREFL0_157") (pintype "bidirectional"))
      (node (ref "U4") (pin "170") (pinfunction "VSS(IO)9_170") (pintype "bidirectional"))
      (node (ref "U4") (pin "22") (pinfunction "VSS1_22") (pintype "bidirectional"))
      (node (ref "U4") (pin "28") (pinfunction "AVSS_USBHS_28") (pintype "bidirectional"))
      (node (ref "U4") (pin "29") (pinfunction "PVSS_USBHS_29") (pintype "bidirectional"))
      (node (ref "U4") (pin "30") (pinfunction "VSS2_USBHS_30") (pintype "bidirectional"))
      (node (ref "U4") (pin "33") (pinfunction "VSS1_USBHS_33") (pintype "bidirectional"))
      (node (ref "U4") (pin "35") (pinfunction "VSSIO_35") (pintype "bidirectional"))
      (node (ref "U4") (pin "45") (pinfunction "VSS_USB_45") (pintype "bidirectional"))
      (node (ref "U4") (pin "60") (pinfunction "VSS(IO)2_60") (pintype "bidirectional"))
      (node (ref "U4") (pin "63") (pinfunction "VSS(IO/DCDC)_63") (pintype "bidirectional"))
      (node (ref "U4") (pin "66") (pinfunction "VCC_DCDC(IO/DCDC)_66") (pintype "bidirectional"))
      (node (ref "U4") (pin "83") (pinfunction "VSS(IO)3_83") (pintype "bidirectional"))
      (node (ref "U4") (pin "98") (pinfunction "VSS(IO)4_98") (pintype "bidirectional"))
      (node (ref "U5") (pin "P$3") (pinfunction "VOUT-_P$3") (pintype "bidirectional"))
      (node (ref "U5") (pin "P$6") (pinfunction "AC_N_P$6") (pintype "bidirectional"))
      (node (ref "U6") (pin "2") (pinfunction "REF_2") (pintype "passive"))
      (node (ref "U6") (pin "3") (pinfunction "VS-_3") (pintype "power_in"))
      (node (ref "U7") (pin "2") (pinfunction "REF_2") (pintype "passive"))
      (node (ref "U7") (pin "3") (pinfunction "VS-_3") (pintype "power_in"))
      (node (ref "X4") (pin "2") (pinfunction "2_2") (pintype "bidirectional"))
      (node (ref "X4") (pin "4") (pinfunction "4_4") (pintype "bidirectional"))
    )
    (net (code "32") (name "GNDE") (class "Default")
      (node (ref "J2") (pin "P$6") (pinfunction "SHIELD1_P$6") (pintype "bidirectional"))
      (node (ref "J2") (pin "P$7") (pinfunction "SHIELD2_P$7") (pintype "bidirectional"))
      (node (ref "J2") (pin "P$8") (pinfunction "SHIELD3_P$8") (pintype "bidirectional"))
      (node (ref "J2") (pin "P$9") (pinfunction "SHIELD4_P$9") (pintype "bidirectional"))
      (node (ref "J3") (pin "SHLD1") (pinfunction "SHIELD_1_SHLD1") (pintype "bidirectional"))
      (node (ref "J3") (pin "SHLD2") (pinfunction "SHIELD_2_SHLD2") (pintype "bidirectional"))
      (node (ref "J4") (pin "13") (pinfunction "GNDE0_13") (pintype "bidirectional"))
      (node (ref "J4") (pin "14") (pinfunction "GNDE1_14") (pintype "bidirectional"))
    )
    (net (code "33") (name "GP4") (class "Default")
      (node (ref "U$1") (pin "P$7") (pinfunction "GP4_P$7") (pintype "bidirectional"))
      (node (ref "U4") (pin "49") (pinfunction "P2_7_49") (pintype "bidirectional"))
    )
    (net (code "34") (name "GP5") (class "Default")
      (node (ref "U$1") (pin "P$29") (pinfunction "GP5_P$29") (pintype "bidirectional"))
      (node (ref "U4") (pin "57") (pinfunction "P3_15_57") (pintype "bidirectional"))
    )
    (net (code "35") (name "GP6") (class "Default")
      (node (ref "U$1") (pin "P$31") (pinfunction "GP6_P$31") (pintype "bidirectional"))
      (node (ref "U4") (pin "59") (pinfunction "P9_1_59") (pintype "bidirectional"))
    )
    (net (code "36") (name "GP12") (class "Default")
      (node (ref "U$1") (pin "P$32") (pinfunction "GP12_P$32") (pintype "bidirectional"))
      (node (ref "U4") (pin "58") (pinfunction "P9_0_58") (pintype "bidirectional"))
    )
    (net (code "37") (name "GP13") (class "Default")
      (node (ref "U$1") (pin "P$33") (pinfunction "GP13_P$33") (pintype "bidirectional"))
      (node (ref "U4") (pin "76") (pinfunction "P3_10_76") (pintype "bidirectional"))
    )
    (net (code "38") (name "GP14") (class "Default")
      (node (ref "U$1") (pin "P$8") (pinfunction "TXO_P$8") (pintype "output"))
      (node (ref "U4") (pin "42") (pinfunction "P4_9_42") (pintype "bidirectional"))
    )
    (net (code "39") (name "GP15") (class "Default")
      (node (ref "U$1") (pin "P$10") (pinfunction "RXI_P$10") (pintype "input"))
      (node (ref "U4") (pin "43") (pinfunction "P4_8_43") (pintype "bidirectional"))
    )
    (net (code "40") (name "GP16") (class "Default")
      (node (ref "U$1") (pin "P$36") (pinfunction "GP16_P$36") (pintype "bidirectional"))
      (node (ref "U4") (pin "79") (pinfunction "P3_7_79") (pintype "bidirectional"))
    )
    (net (code "41") (name "GP17") (class "Default")
      (node (ref "U$1") (pin "P$11") (pinfunction "GP17_P$11") (pintype "bidirectional"))
      (node (ref "U4") (pin "51") (pinfunction "P2_5_51") (pintype "bidirectional"))
    )
    (net (code "42") (name "GP18") (class "Default")
      (node (ref "U$1") (pin "P$12") (pinfunction "GP18#_P$12") (pintype "bidirectional"))
      (node (ref "U4") (pin "50") (pinfunction "P2_6_50") (pintype "bidirectional"))
    )
    (net (code "43") (name "GP19") (class "Default")
      (node (ref "U$1") (pin "P$35") (pinfunction "GP19_P$35") (pintype "bidirectional"))
      (node (ref "U4") (pin "77") (pinfunction "P3_9_77") (pintype "bidirectional"))
    )
    (net (code "44") (name "GP20") (class "Default")
      (node (ref "U$1") (pin "P$38") (pinfunction "GP20_P$38") (pintype "bidirectional"))
      (node (ref "U4") (pin "81") (pinfunction "P3_5_81") (pintype "bidirectional"))
    )
    (net (code "45") (name "GP21") (class "Default")
      (node (ref "U$1") (pin "P$40") (pinfunction "GP21_P$40") (pintype "bidirectional"))
      (node (ref "U4") (pin "82") (pinfunction "P3_4_82") (pintype "bidirectional"))
    )
    (net (code "46") (name "GP22") (class "Default")
      (node (ref "U$1") (pin "P$15") (pinfunction "GP22_P$15") (pintype "bidirectional"))
      (node (ref "U4") (pin "72") (pinfunction "P9_6_72") (pintype "bidirectional"))
    )
    (net (code "47") (name "GP23") (class "Default")
      (node (ref "U$1") (pin "P$16") (pinfunction "GP23_P$16") (pintype "bidirectional"))
      (node (ref "U4") (pin "71") (pinfunction "P9_7_71") (pintype "bidirectional"))
    )
    (net (code "48") (name "GP24") (class "Default")
      (node (ref "U$1") (pin "P$18") (pinfunction "GP24_P$18") (pintype "bidirectional"))
      (node (ref "U4") (pin "73") (pinfunction "P9_5_73") (pintype "bidirectional"))
    )
    (net (code "49") (name "GP25") (class "Default")
      (node (ref "U$1") (pin "P$22") (pinfunction "GP25_P$22") (pintype "bidirectional"))
      (node (ref "U4") (pin "56") (pinfunction "P3_14_56") (pintype "bidirectional"))
    )
    (net (code "50") (name "GP26") (class "Default")
      (node (ref "U$1") (pin "P$37") (pinfunction "GP26_P$37") (pintype "bidirectional"))
      (node (ref "U4") (pin "80") (pinfunction "P3_6_80") (pintype "bidirectional"))
    )
    (net (code "51") (name "GP27") (class "Default")
      (node (ref "U$1") (pin "P$13") (pinfunction "GP27_P$13") (pintype "bidirectional"))
      (node (ref "U4") (pin "70") (pinfunction "P9_8_70") (pintype "bidirectional"))
    )
    (net (code "52") (name "ID") (class "Default")
      (node (ref "J2") (pin "P$4") (pinfunction "ID_P$4") (pintype "bidirectional"))
    )
    (net (code "53") (name "ID_SC") (class "Default")
      (node (ref "U$1") (pin "P$28") (pinfunction "ID_SC_P$28") (pintype "bidirectional"))
      (node (ref "U4") (pin "93") (pinfunction "P1_12_93") (pintype "bidirectional"))
    )
    (net (code "54") (name "ID_SD") (class "Default")
      (node (ref "U$1") (pin "P$27") (pinfunction "ID_SD_P$27") (pintype "bidirectional"))
      (node (ref "U4") (pin "92") (pinfunction "P1_11_92") (pintype "bidirectional"))
    )
    (net (code "55") (name "IIC_0_SCL") (class "Default")
      (node (ref "U$1") (pin "P$5") (pinfunction "SCL_P$5") (pintype "bidirectional"))
      (node (ref "U4") (pin "1") (pinfunction "P4_0_1") (pintype "bidirectional"))
    )
    (net (code "56") (name "IIC_0_SDA") (class "Default")
      (node (ref "U$1") (pin "P$3") (pinfunction "SDA_P$3") (pintype "bidirectional"))
      (node (ref "U4") (pin "2") (pinfunction "P4_1_2") (pintype "bidirectional"))
    )
    (net (code "57") (name "IRQ0") (class "Default")
      (node (ref "U$2") (pin "P10") (pinfunction "IRQ0_P10") (pintype "bidirectional"))
      (node (ref "U4") (pin "86") (pinfunction "P3_2_86") (pintype "bidirectional"))
    )
    (net (code "58") (name "IRQ1") (class "Default")
      (node (ref "U$2") (pin "P11") (pinfunction "IRQ1_P11") (pintype "bidirectional"))
      (node (ref "U4") (pin "87") (pinfunction "P3_1_87") (pintype "bidirectional"))
    )
    (net (code "59") (name "LED1{slash}SPEED") (class "Default")
      (node (ref "J4") (pin "11") (pinfunction "YLO_11") (pintype "bidirectional"))
      (node (ref "U3") (pin "23") (pinfunction "LED0/ANEN_SPEED_23") (pintype "bidirectional"))
    )
    (net (code "60") (name "M0_STEP") (class "Default")
      (node (ref "U4") (pin "16") (pinfunction "PB_0_16") (pintype "bidirectional"))
    )
    (net (code "61") (name "NC") (class "Default")
      (node (ref "J4") (pin "7") (pinfunction "P7_7") (pintype "bidirectional"))
    )
    (net (code "62") (name "Net-(C16-1)") (class "Default")
      (node (ref "C16") (pin "P$1") (pinfunction "1_P$1") (pintype "passive"))
      (node (ref "J2") (pin "P$1") (pinfunction "VBUS_P$1") (pintype "bidirectional"))
      (node (ref "R4") (pin "P$2") (pinfunction "2_P$2") (pintype "passive"))
      (node (ref "R7") (pin "P$2") (pinfunction "2_P$2") (pintype "passive"))
    )
    (net (code "63") (name "Net-(C31-1)") (class "Default")
      (node (ref "C31") (pin "P$1") (pinfunction "1_P$1") (pintype "passive"))
      (node (ref "U4") (pin "62") (pinfunction "VCL1_62") (pintype "bidirectional"))
    )
    (net (code "64") (name "Net-(C37-2)") (class "Default")
      (node (ref "C37") (pin "P$2") (pinfunction "2_P$2") (pintype "passive"))
      (node (ref "U4") (pin "148") (pinfunction "VCL2_148") (pintype "bidirectional"))
    )
    (net (code "65") (name "Net-(C38-1)") (class "Default")
      (node (ref "C38") (pin "P$1") (pinfunction "1_P$1") (pintype "passive"))
      (node (ref "U4") (pin "19") (pinfunction "VCLO_19") (pintype "bidirectional"))
    )
    (net (code "66") (name "Net-(C44-1)") (class "Default")
      (node (ref "C43") (pin "1") (pinfunction "1_1") (pintype "passive"))
      (node (ref "C44") (pin "P$1") (pinfunction "1_P$1") (pintype "passive"))
      (node (ref "FB2/2") (pin "2") (pinfunction "P$2_2") (pintype "bidirectional"))
      (node (ref "U3") (pin "2") (pinfunction "VDDA_3.3_2") (pintype "power_in"))
    )
    (net (code "67") (name "Net-(J2-D+)") (class "Default")
      (node (ref "J2") (pin "P$3") (pinfunction "D+_P$3") (pintype "bidirectional"))
      (node (ref "R6") (pin "P$2") (pinfunction "2_P$2") (pintype "passive"))
    )
    (net (code "68") (name "Net-(J2-D-)") (class "Default")
      (node (ref "J2") (pin "P$2") (pinfunction "D-_P$2") (pintype "bidirectional"))
      (node (ref "R5") (pin "P$2") (pinfunction "2_P$2") (pintype "passive"))
    )
    (net (code "69") (name "Net-(R8-2)") (class "Default")
      (node (ref "LED3") (pin "A") (pinfunction "A_A") (pintype "passive"))
      (node (ref "R8") (pin "P$2") (pinfunction "2_P$2") (pintype "passive"))
    )
    (net (code "70") (name "Net-(R9-2)") (class "Default")
      (node (ref "LED4") (pin "A") (pinfunction "A_A") (pintype "passive"))
      (node (ref "R9") (pin "P$2") (pinfunction "2_P$2") (pintype "passive"))
    )
    (net (code "71") (name "Net-(R16-2)") (class "Default")
      (node (ref "R16") (pin "P$2") (pinfunction "2_P$2") (pintype "passive"))
      (node (ref "U4") (pin "65") (pinfunction "VLO2(DCDC)_65") (pintype "bidirectional"))
    )
    (net (code "72") (name "Net-(R17-2)") (class "Default")
      (node (ref "R17") (pin "P$2") (pinfunction "2_P$2") (pintype "passive"))
      (node (ref "U4") (pin "64") (pinfunction "VLO1(DCDC)_64") (pintype "bidirectional"))
    )
    (net (code "73") (name "Net-(R19-2)") (class "Default")
      (node (ref "R19") (pin "P$2") (pinfunction "2_P$2") (pintype "passive"))
      (node (ref "U4") (pin "27") (pinfunction "USBHS_RREF_27") (pintype "bidirectional"))
    )
    (net (code "74") (name "P0_02") (class "Default")
      (node (ref "J1") (pin "P$6") (pinfunction "P$6_P$6") (pintype "bidirectional"))
      (node (ref "U4") (pin "167") (pinfunction "P0_2/AN002_167") (pintype "bidirectional"))
    )
    (net (code "75") (name "P0_03") (class "Default")
      (node (ref "J1") (pin "P$5") (pinfunction "P$5_P$5") (pintype "bidirectional"))
      (node (ref "U4") (pin "166") (pinfunction "P0_3/PGAVSS000_166") (pintype "bidirectional"))
    )
    (net (code "76") (name "P0_04") (class "Default")
      (node (ref "J1") (pin "P$8") (pinfunction "P$8_P$8") (pintype "bidirectional"))
      (node (ref "U4") (pin "165") (pinfunction "P0_4/AN100_165") (pintype "bidirectional"))
    )
    (net (code "77") (name "P0_07") (class "Default")
      (node (ref "J1") (pin "P$7") (pinfunction "P$7_P$7") (pintype "bidirectional"))
      (node (ref "U4") (pin "162") (pinfunction "P0_7/PGVSS100_162") (pintype "bidirectional"))
    )
    (net (code "78") (name "P0_14") (class "Default")
      (node (ref "J1") (pin "P$10") (pinfunction "P$10_P$10") (pintype "bidirectional"))
      (node (ref "U4") (pin "152") (pinfunction "P0_14/DA0/AN005/AN105_152") (pintype "bidirectional"))
    )
    (net (code "79") (name "P0_15") (class "Default")
      (node (ref "J1") (pin "P$9") (pinfunction "P$9_P$9") (pintype "bidirectional"))
      (node (ref "U4") (pin "151") (pinfunction "P0_15/DA1/AN006/AN106_151") (pintype "bidirectional"))
    )
    (net (code "80") (name "P1_05") (class "Default")
      (node (ref "U4") (pin "127") (pinfunction "P1_5_127") (pintype "bidirectional"))
    )
    (net (code "81") (name "P1_13") (class "Default")
      (node (ref "U4") (pin "94") (pinfunction "P1_13_94") (pintype "bidirectional"))
    )
    (net (code "82") (name "P1_14") (class "Default")
      (node (ref "U4") (pin "95") (pinfunction "P1_14_95") (pintype "bidirectional"))
    )
    (net (code "83") (name "P1_15") (class "Default")
      (node (ref "U4") (pin "96") (pinfunction "P1_15_96") (pintype "bidirectional"))
    )
    (net (code "84") (name "P2_00") (class "Default")
      (node (ref "U4") (pin "69") (pinfunction "P2_0(INPUT_ONLY)_69") (pintype "bidirectional"))
    )
    (net (code "85") (name "P2_01") (class "Default")
      (node (ref "U4") (pin "68") (pinfunction "P2_1/MD_68") (pintype "bidirectional"))
    )
    (net (code "86") (name "P3_03") (class "Default")
      (node (ref "U4") (pin "85") (pinfunction "P3_3_85") (pintype "bidirectional"))
    )
    (net (code "87") (name "P3_11") (class "Default")
      (node (ref "U4") (pin "75") (pinfunction "P3_11_75") (pintype "bidirectional"))
    )
    (net (code "88") (name "P4_02") (class "Default")
      (node (ref "U4") (pin "3") (pinfunction "P4_2_3") (pintype "bidirectional"))
    )
    (net (code "89") (name "P4_10") (class "Default")
      (node (ref "U4") (pin "41") (pinfunction "P4_10_41") (pintype "bidirectional"))
    )
    (net (code "90") (name "P4_11") (class "Default")
      (node (ref "U4") (pin "40") (pinfunction "P4_11_40") (pintype "bidirectional"))
    )
    (net (code "91") (name "P4_12") (class "Default")
      (node (ref "U4") (pin "39") (pinfunction "P4_12_39") (pintype "bidirectional"))
    )
    (net (code "92") (name "P4_13") (class "Default")
      (node (ref "U4") (pin "38") (pinfunction "P4_13_38") (pintype "bidirectional"))
    )
    (net (code "93") (name "P4_14") (class "Default")
      (node (ref "U4") (pin "37") (pinfunction "P4_14_37") (pintype "bidirectional"))
    )
    (net (code "94") (name "P4_15") (class "Default")
      (node (ref "U4") (pin "36") (pinfunction "P4_15_36") (pintype "bidirectional"))
    )
    (net (code "95") (name "P5_00") (class "Default")
      (node (ref "J1") (pin "P$17") (pinfunction "P$17_P$17") (pintype "bidirectional"))
      (node (ref "U4") (pin "140") (pinfunction "P5_0/AN016_140") (pintype "bidirectional"))
    )
    (net (code "96") (name "P5_01") (class "Default")
      (node (ref "J1") (pin "P$18") (pinfunction "P$18_P$18") (pintype "bidirectional"))
      (node (ref "U4") (pin "141") (pinfunction "P5_1/AN116_141") (pintype "bidirectional"))
    )
    (net (code "97") (name "P5_02") (class "Default")
      (node (ref "J1") (pin "P$15") (pinfunction "P$15_P$15") (pintype "bidirectional"))
      (node (ref "U4") (pin "142") (pinfunction "P5_2/AN017_142") (pintype "bidirectional"))
    )
    (net (code "98") (name "P5_03") (class "Default")
      (node (ref "J1") (pin "P$16") (pinfunction "P$16_P$16") (pintype "bidirectional"))
      (node (ref "U4") (pin "143") (pinfunction "P5_3/AN117_143") (pintype "bidirectional"))
    )
    (net (code "99") (name "P5_04") (class "Default")
      (node (ref "J1") (pin "P$13") (pinfunction "P$13_P$13") (pintype "bidirectional"))
      (node (ref "U4") (pin "144") (pinfunction "P5_4/AN018_144") (pintype "bidirectional"))
    )
    (net (code "100") (name "P5_05") (class "Default")
      (node (ref "J1") (pin "P$14") (pinfunction "P$14_P$14") (pintype "bidirectional"))
      (node (ref "U4") (pin "145") (pinfunction "P5_5/AN118_145") (pintype "bidirectional"))
    )
    (net (code "101") (name "P5_06") (class "Default")
      (node (ref "J1") (pin "P$11") (pinfunction "P$11_P$11") (pintype "bidirectional"))
      (node (ref "U4") (pin "146") (pinfunction "P5_6/AN019_146") (pintype "bidirectional"))
    )
    (net (code "102") (name "P5_07") (class "Default")
      (node (ref "J1") (pin "P$12") (pinfunction "P$12_P$12") (pintype "bidirectional"))
      (node (ref "U4") (pin "147") (pinfunction "P5_7/AN119_147") (pintype "bidirectional"))
    )
    (net (code "103") (name "P5_11") (class "Default")
      (node (ref "J1") (pin "P$2") (pinfunction "P$2_P$2") (pintype "bidirectional"))
      (node (ref "U4") (pin "176") (pinfunction "P5_11_176") (pintype "bidirectional"))
    )
    (net (code "104") (name "P5_12") (class "Default")
      (node (ref "J1") (pin "P$1") (pinfunction "P$1_P$1") (pintype "bidirectional"))
      (node (ref "U4") (pin "175") (pinfunction "P5_12_175") (pintype "bidirectional"))
    )
    (net (code "105") (name "P5_13") (class "Default")
      (node (ref "J1") (pin "P$4") (pinfunction "P$4_P$4") (pintype "bidirectional"))
      (node (ref "U4") (pin "174") (pinfunction "P5_13_174") (pintype "bidirectional"))
    )
    (net (code "106") (name "P6_02") (class "Default")
      (node (ref "U4") (pin "120") (pinfunction "P6_2_120") (pintype "bidirectional"))
    )
    (net (code "107") (name "P6_03") (class "Default")
      (node (ref "U4") (pin "119") (pinfunction "P6_3_119") (pintype "bidirectional"))
    )
    (net (code "108") (name "P6_04") (class "Default")
      (node (ref "U4") (pin "118") (pinfunction "P6_4_118") (pintype "bidirectional"))
    )
    (net (code "109") (name "P6_05") (class "Default")
      (node (ref "U4") (pin "117") (pinfunction "P6_5_117") (pintype "bidirectional"))
    )
    (net (code "110") (name "P6_06") (class "Default")
      (node (ref "U4") (pin "116") (pinfunction "P6_6_116") (pintype "bidirectional"))
    )
    (net (code "111") (name "P6_07") (class "Default")
      (node (ref "U4") (pin "115") (pinfunction "P6_7_115") (pintype "bidirectional"))
    )
    (net (code "112") (name "P6_08") (class "Default")
      (node (ref "U4") (pin "99") (pinfunction "P6_8_99") (pintype "bidirectional"))
    )
    (net (code "113") (name "P6_09") (class "Default")
      (node (ref "U4") (pin "100") (pinfunction "P6_9_100") (pintype "bidirectional"))
    )
    (net (code "114") (name "P6_10") (class "Default")
      (node (ref "U4") (pin "101") (pinfunction "P6_10_101") (pintype "bidirectional"))
    )
    (net (code "115") (name "P6_11") (class "Default")
      (node (ref "U4") (pin "102") (pinfunction "P6_11_102") (pintype "bidirectional"))
    )
    (net (code "116") (name "P6_12") (class "Default")
      (node (ref "U4") (pin "103") (pinfunction "P6_12_103") (pintype "bidirectional"))
    )
    (net (code "117") (name "P6_13") (class "Default")
      (node (ref "U4") (pin "104") (pinfunction "P6_13_104") (pintype "bidirectional"))
    )
    (net (code "118") (name "P6_14") (class "Default")
      (node (ref "U4") (pin "105") (pinfunction "P6_14_105") (pintype "bidirectional"))
    )
    (net (code "119") (name "P6_15") (class "Default")
      (node (ref "U4") (pin "106") (pinfunction "P6_15_106") (pintype "bidirectional"))
    )
    (net (code "120") (name "P7_06") (class "Default")
      (node (ref "U4") (pin "14") (pinfunction "P7_6_14") (pintype "bidirectional"))
    )
    (net (code "121") (name "P7_07") (class "Default")
      (node (ref "U4") (pin "15") (pinfunction "P7_7_15") (pintype "bidirectional"))
    )
    (net (code "122") (name "P8_03") (class "Default")
      (node (ref "U4") (pin "136") (pinfunction "P8_3_136") (pintype "bidirectional"))
    )
    (net (code "123") (name "P8_04") (class "Default")
      (node (ref "U4") (pin "137") (pinfunction "P8_4_137") (pintype "bidirectional"))
    )
    (net (code "124") (name "P8_05") (class "Default")
      (node (ref "J1") (pin "P$3") (pinfunction "P$3_P$3") (pintype "bidirectional"))
      (node (ref "U4") (pin "173") (pinfunction "P8_5_173") (pintype "bidirectional"))
    )
    (net (code "125") (name "PA_00") (class "Default")
      (node (ref "U4") (pin "114") (pinfunction "PA_0_114") (pintype "bidirectional"))
    )
    (net (code "126") (name "PA_01") (class "Default")
      (node (ref "U4") (pin "113") (pinfunction "PA_1_113") (pintype "bidirectional"))
    )
    (net (code "127") (name "PA_08") (class "Default")
      (node (ref "U4") (pin "107") (pinfunction "PA_8_107") (pintype "bidirectional"))
    )
    (net (code "128") (name "PA_09") (class "Default")
      (node (ref "U4") (pin "108") (pinfunction "PA_9_108") (pintype "bidirectional"))
    )
    (net (code "129") (name "PA_10") (class "Default")
      (node (ref "U4") (pin "109") (pinfunction "PA_10_109") (pintype "bidirectional"))
    )
    (net (code "130") (name "PM0") (class "Default")
      (node (ref "U$2") (pin "P12") (pinfunction "PM0_P12") (pintype "bidirectional"))
      (node (ref "U4") (pin "126") (pinfunction "P1_6_126") (pintype "bidirectional"))
    )
    (net (code "131") (name "PM1") (class "Default")
      (node (ref "U$2") (pin "P13") (pinfunction "PM1_P13") (pintype "bidirectional"))
      (node (ref "U4") (pin "125") (pinfunction "P1_7_125") (pintype "bidirectional"))
    )
    (net (code "132") (name "R51") (class "Default")
      (node (ref "J4") (pin "12") (pinfunction "YHI_12") (pintype "bidirectional"))
      (node (ref "R23") (pin "P$1") (pinfunction "1_P$1") (pintype "passive"))
    )
    (net (code "133") (name "R52") (class "Default")
      (node (ref "J4") (pin "9") (pinfunction "GHI_9") (pintype "bidirectional"))
      (node (ref "R24") (pin "P$1") (pinfunction "1_P$1") (pintype "passive"))
    )
    (net (code "134") (name "RESET") (class "Default")
      (node (ref "C57") (pin "P$1") (pinfunction "1_P$1") (pintype "passive"))
      (node (ref "J11") (pin "9") (pinfunction "9_9") (pintype "passive"))
      (node (ref "R18") (pin "P$1") (pinfunction "1_P$1") (pintype "passive"))
      (node (ref "U4") (pin "67") (pinfunction "RES#_67") (pintype "bidirectional"))
    )
    (net (code "135") (name "REXT") (class "Default")
      (node (ref "C47") (pin "P$1") (pinfunction "1_P$1") (pintype "passive"))
      (node (ref "R25") (pin "P$2") (pinfunction "2_P$2") (pintype "passive"))
      (node (ref "U3") (pin "9") (pinfunction "REXT_9") (pintype "input"))
    )
    (net (code "136") (name "RST") (class "Default")
      (node (ref "U$2") (pin "P20") (pinfunction "RST_P20") (pintype "bidirectional"))
      (node (ref "U4") (pin "121") (pinfunction "P6_1_121") (pintype "bidirectional"))
    )
    (net (code "137") (name "RXD0") (class "Default")
      (node (ref "R31") (pin "P$2") (pinfunction "2_P$2") (pintype "passive"))
      (node (ref "U3") (pin "13") (pinfunction "RXD0_13") (pintype "bidirectional"))
    )
    (net (code "138") (name "RXD1") (class "Default")
      (node (ref "R30") (pin "P$2") (pinfunction "2_P$2") (pintype "passive"))
      (node (ref "U3") (pin "12") (pinfunction "RXD1_12") (pintype "bidirectional"))
    )
    (net (code "139") (name "RXER") (class "Default")
      (node (ref "R32") (pin "P$2") (pinfunction "2_P$2") (pintype "passive"))
      (node (ref "U3") (pin "17") (pinfunction "RXER_17") (pintype "bidirectional"))
    )
    (net (code "140") (name "RXM") (class "Default")
      (node (ref "J4") (pin "6") (pinfunction "RD-_6") (pintype "bidirectional"))
      (node (ref "U3") (pin "3") (pinfunction "RXM_3") (pintype "bidirectional"))
    )
    (net (code "141") (name "RXP") (class "Default")
      (node (ref "J4") (pin "3") (pinfunction "RD+_3") (pintype "bidirectional"))
      (node (ref "U3") (pin "4") (pinfunction "RXP_4") (pintype "bidirectional"))
    )
    (net (code "142") (name "SPI_0_CS_0") (class "Default")
      (node (ref "U$2") (pin "P16") (pinfunction "CS_P16") (pintype "bidirectional"))
      (node (ref "U4") (pin "129") (pinfunction "P1_3_129") (pintype "bidirectional"))
    )
    (net (code "143") (name "SPI_0_MISO") (class "Default")
      (node (ref "U$2") (pin "P18") (pinfunction "SDO_P18") (pintype "bidirectional"))
      (node (ref "U4") (pin "132") (pinfunction "P1_0_132") (pintype "bidirectional"))
    )
    (net (code "144") (name "SPI_0_MOSI") (class "Default")
      (node (ref "U$2") (pin "P15") (pinfunction "SDI_P15") (pintype "bidirectional"))
      (node (ref "U4") (pin "131") (pinfunction "P1_1_131") (pintype "bidirectional"))
    )
    (net (code "145") (name "SPI_0_SCLK") (class "Default")
      (node (ref "U$2") (pin "P17") (pinfunction "SCLK_P17") (pintype "bidirectional"))
      (node (ref "U4") (pin "130") (pinfunction "P1_2_130") (pintype "bidirectional"))
    )
    (net (code "146") (name "SPI_1_CS_0") (class "Default")
      (node (ref "U$1") (pin "P$24") (pinfunction "CE0_P$24") (pintype "output"))
      (node (ref "U4") (pin "55") (pinfunction "P3_13_55") (pintype "bidirectional"))
    )
    (net (code "147") (name "SPI_1_CS_1") (class "Default")
      (node (ref "U$1") (pin "P$26") (pinfunction "CE1_P$26") (pintype "output"))
      (node (ref "U4") (pin "74") (pinfunction "P3_12_74") (pintype "bidirectional"))
    )
    (net (code "148") (name "SPI_1_MISO") (class "Default")
      (node (ref "U$1") (pin "P$21") (pinfunction "MISO_P$21") (pintype "input"))
      (node (ref "U4") (pin "54") (pinfunction "P2_2_54") (pintype "bidirectional"))
    )
    (net (code "149") (name "SPI_1_MOSI") (class "Default")
      (node (ref "U$1") (pin "P$19") (pinfunction "MOSI_P$19") (pintype "output"))
      (node (ref "U4") (pin "53") (pinfunction "P2_3_53") (pintype "bidirectional"))
    )
    (net (code "150") (name "SPI_1_SCLK") (class "Default")
      (node (ref "U$1") (pin "P$23") (pinfunction "SCLK_P$23") (pintype "output"))
      (node (ref "U4") (pin "52") (pinfunction "P2_4_52") (pintype "bidirectional"))
    )
    (net (code "151") (name "TCK") (class "Default")
      (node (ref "J11") (pin "7") (pinfunction "7_7") (pintype "passive"))
      (node (ref "U4") (pin "88") (pinfunction "P3_0_88") (pintype "bidirectional"))
    )
    (net (code "152") (name "TDI") (class "Default")
      (node (ref "J11") (pin "1") (pinfunction "1_1") (pintype "passive"))
      (node (ref "U4") (pin "91") (pinfunction "P1_10_91") (pintype "bidirectional"))
    )
    (net (code "153") (name "TDO") (class "Default")
      (node (ref "J11") (pin "3") (pinfunction "3_3") (pintype "passive"))
      (node (ref "U4") (pin "90") (pinfunction "P1_9_90") (pintype "bidirectional"))
    )
    (net (code "154") (name "TMS") (class "Default")
      (node (ref "J11") (pin "5") (pinfunction "5_5") (pintype "passive"))
      (node (ref "U4") (pin "89") (pinfunction "P1_8_89") (pintype "bidirectional"))
    )
    (net (code "155") (name "TXM") (class "Default")
      (node (ref "J4") (pin "2") (pinfunction "TD-_2") (pintype "bidirectional"))
      (node (ref "U3") (pin "5") (pinfunction "TXM_5") (pintype "bidirectional"))
    )
    (net (code "156") (name "TXP") (class "Default")
      (node (ref "J4") (pin "1") (pinfunction "TD+_1") (pintype "bidirectional"))
      (node (ref "U3") (pin "6") (pinfunction "TXP_6") (pintype "bidirectional"))
    )
    (net (code "157") (name "UC") (class "Default")
      (node (ref "C20") (pin "P$1") (pinfunction "P$1_P$1") (pintype "bidirectional"))
      (node (ref "U$2") (pin "P22") (pinfunction "VAC_240_P22") (pintype "bidirectional"))
      (node (ref "U$7") (pin "P$1") (pinfunction "P$1_P$1") (pintype "bidirectional"))
      (node (ref "U5") (pin "P$5") (pinfunction "AC_L_P$5") (pintype "bidirectional"))
    )
    (net (code "158") (name "USBHS_FAULT") (class "Default")
      (node (ref "R12") (pin "P$1") (pinfunction "1_P$1") (pintype "passive"))
      (node (ref "U2") (pin "3") (pinfunction "FLG_3") (pintype "input"))
      (node (ref "U4") (pin "78") (pinfunction "P3_8_78") (pintype "bidirectional"))
    )
    (net (code "159") (name "USBHS_N") (class "Default")
      (node (ref "J3") (pin "D-") (pinfunction "D-_D-") (pintype "bidirectional"))
      (node (ref "U4") (pin "31") (pinfunction "USBHS_DM_31") (pintype "bidirectional"))
    )
    (net (code "160") (name "USBHS_P") (class "Default")
      (node (ref "J3") (pin "D+") (pinfunction "D+_D+") (pintype "bidirectional"))
      (node (ref "U4") (pin "32") (pinfunction "USBHS_DP_32") (pintype "bidirectional"))
    )
    (net (code "161") (name "USBHS_VBUS") (class "Default")
      (node (ref "C11") (pin "P$1") (pinfunction "1_P$1") (pintype "passive"))
      (node (ref "C15") (pin "1") (pinfunction "1_1") (pintype "passive"))
      (node (ref "J3") (pin "VBUS") (pinfunction "VBUS_VBUS") (pintype "power_in"))
      (node (ref "U2") (pin "5") (pinfunction "OUT_5") (pintype "input"))
      (node (ref "U4") (pin "17") (pinfunction "PB_1_17") (pintype "bidirectional"))
    )
    (net (code "162") (name "USBHS_VBUSEN") (class "Default")
      (node (ref "R1") (pin "P$1") (pinfunction "1_P$1") (pintype "passive"))
      (node (ref "U2") (pin "1") (pinfunction "EN_1") (pintype "input"))
    )
    (net (code "163") (name "USB_N") (class "Default")
      (node (ref "R5") (pin "P$1") (pinfunction "1_P$1") (pintype "passive"))
      (node (ref "U4") (pin "46") (pinfunction "USB_DM_46") (pintype "bidirectional"))
    )
    (net (code "164") (name "USB_P") (class "Default")
      (node (ref "R6") (pin "P$1") (pinfunction "1_P$1") (pintype "passive"))
      (node (ref "U4") (pin "47") (pinfunction "USB_DP_47") (pintype "bidirectional"))
    )
    (net (code "165") (name "USB_VBUS_B") (class "Default")
      (node (ref "R4") (pin "P$1") (pinfunction "1_P$1") (pintype "passive"))
      (node (ref "U4") (pin "44") (pinfunction "P4_7_44") (pintype "bidirectional"))
    )
    (net (code "166") (name "VCC") (class "Default")
      (node (ref "C21") (pin "P$1") (pinfunction "1_P$1") (pintype "passive"))
      (node (ref "C22") (pin "P$1") (pinfunction "1_P$1") (pintype "passive"))
      (node (ref "C23") (pin "1") (pinfunction "1_1") (pintype "passive"))
      (node (ref "C24") (pin "P$1") (pinfunction "1_P$1") (pintype "passive"))
      (node (ref "IC3") (pin "1") (pinfunction "IN_1") (pintype "input"))
      (node (ref "IC4") (pin "1") (pinfunction "IN_1") (pintype "input"))
      (node (ref "U$8") (pin "P+") (pinfunction "+_P+") (pintype "passive"))
      (node (ref "U5") (pin "P$2") (pinfunction "VOUT+_P$2") (pintype "bidirectional"))
    )
    (net (code "167") (name "VCL_F(FLASH)") (class "Default")
      (node (ref "C36") (pin "P$2") (pinfunction "2_P$2") (pintype "passive"))
      (node (ref "U4") (pin "112") (pinfunction "VCL_F(FLASH)_112") (pintype "bidirectional"))
    )
    (net (code "168") (name "VDD") (class "Default")
      (node (ref "C1") (pin "P$2") (pinfunction "2_P$2") (pintype "passive"))
      (node (ref "C10") (pin "P$2") (pinfunction "2_P$2") (pintype "passive"))
      (node (ref "C13") (pin "P$2") (pinfunction "2_P$2") (pintype "passive"))
      (node (ref "C14") (pin "P$2") (pinfunction "2_P$2") (pintype "passive"))
      (node (ref "C19") (pin "P$1") (pinfunction "1_P$1") (pintype "passive"))
      (node (ref "C2") (pin "P$2") (pinfunction "2_P$2") (pintype "passive"))
      (node (ref "C25") (pin "P$1") (pinfunction "1_P$1") (pintype "passive"))
      (node (ref "C26") (pin "1") (pinfunction "1_1") (pintype "passive"))
      (node (ref "C29") (pin "P$1") (pinfunction "1_P$1") (pintype "passive"))
      (node (ref "C30") (pin "P$2") (pinfunction "2_P$2") (pintype "passive"))
      (node (ref "C32") (pin "P$1") (pinfunction "1_P$1") (pintype "passive"))
      (node (ref "C48") (pin "1") (pinfunction "1_1") (pintype "passive"))
      (node (ref "C49") (pin "P$1") (pinfunction "1_P$1") (pintype "passive"))
      (node (ref "C54") (pin "P$2") (pinfunction "2_P$2") (pintype "passive"))
      (node (ref "C55") (pin "P$2") (pinfunction "2_P$2") (pintype "passive"))
      (node (ref "C56") (pin "P$2") (pinfunction "2_P$2") (pintype "passive"))
      (node (ref "C58") (pin "P$1") (pinfunction "1_P$1") (pintype "passive"))
      (node (ref "C59") (pin "P$1") (pinfunction "1_P$1") (pintype "passive"))
      (node (ref "C60") (pin "P$1") (pinfunction "1_P$1") (pintype "passive"))
      (node (ref "C61") (pin "P$2") (pinfunction "2_P$2") (pintype "passive"))
      (node (ref "C62") (pin "P$1") (pinfunction "1_P$1") (pintype "passive"))
      (node (ref "C63") (pin "P$1") (pinfunction "1_P$1") (pintype "passive"))
      (node (ref "FB2/2") (pin "1") (pinfunction "P$1_1") (pintype "bidirectional"))
      (node (ref "IC4") (pin "3") (pinfunction "OUT_3") (pintype "output"))
      (node (ref "J1") (pin "P$20") (pinfunction "P$20_P$20") (pintype "bidirectional"))
      (node (ref "J11") (pin "2") (pinfunction "2_2") (pintype "passive"))
      (node (ref "J11") (pin "4") (pinfunction "4_4") (pintype "passive"))
      (node (ref "R18") (pin "P$2") (pinfunction "2_P$2") (pintype "passive"))
      (node (ref "R23") (pin "P$2") (pinfunction "2_P$2") (pintype "passive"))
      (node (ref "R24") (pin "P$2") (pinfunction "2_P$2") (pintype "passive"))
      (node (ref "R26") (pin "P$2") (pinfunction "2_P$2") (pintype "passive"))
      (node (ref "R27") (pin "P$2") (pinfunction "2_P$2") (pintype "passive"))
      (node (ref "R28") (pin "P$2") (pinfunction "2_P$2") (pintype "passive"))
      (node (ref "R29") (pin "P$2") (pinfunction "2_P$2") (pintype "passive"))
      (node (ref "R8") (pin "P$1") (pinfunction "1_P$1") (pintype "passive"))
      (node (ref "U$1") (pin "P$1") (pinfunction "3.3V_P$1") (pintype "power_in"))
      (node (ref "U$1") (pin "P$17") (pinfunction "3.3V_P$17") (pintype "power_in"))
      (node (ref "U$2") (pin "P19") (pinfunction "VDD_P19") (pintype "bidirectional"))
      (node (ref "U3") (pin "14") (pinfunction "VDDIO_14") (pintype "power_in"))
      (node (ref "U4") (pin "110") (pinfunction "VCC(IO)5_110") (pintype "bidirectional"))
      (node (ref "U4") (pin "123") (pinfunction "VCC(IO)6_123") (pintype "bidirectional"))
      (node (ref "U4") (pin "138") (pinfunction "VCC(IO)7_138") (pintype "bidirectional"))
      (node (ref "U4") (pin "149") (pinfunction "VCC(IO)8_149") (pintype "bidirectional"))
      (node (ref "U4") (pin "154") (pinfunction "VREFH_154") (pintype "bidirectional"))
      (node (ref "U4") (pin "155") (pinfunction "AVCC0_155") (pintype "bidirectional"))
      (node (ref "U4") (pin "158") (pinfunction "VREFH0_158") (pintype "bidirectional"))
      (node (ref "U4") (pin "171") (pinfunction "VCC(IO)9_171") (pintype "bidirectional"))
      (node (ref "U4") (pin "25") (pinfunction "VCC1_25") (pintype "bidirectional"))
      (node (ref "U4") (pin "26") (pinfunction "AVCC_SUBHS_26") (pintype "bidirectional"))
      (node (ref "U4") (pin "34") (pinfunction "VCC_USBHS_34") (pintype "bidirectional"))
      (node (ref "U4") (pin "48") (pinfunction "VCC_USB_48") (pintype "bidirectional"))
      (node (ref "U4") (pin "61") (pinfunction "VCC(IO)2_61") (pintype "bidirectional"))
      (node (ref "U4") (pin "84") (pinfunction "VCC(IO)3_84") (pintype "bidirectional"))
      (node (ref "U4") (pin "97") (pinfunction "VCC(IO)4_97") (pintype "bidirectional"))
      (node (ref "U6") (pin "7") (pinfunction "+VS_7") (pintype "power_in"))
      (node (ref "U7") (pin "7") (pinfunction "+VS_7") (pintype "power_in"))
    )
    (net (code "169") (name "VDD5") (class "Default")
      (node (ref "C27") (pin "P$1") (pinfunction "1_P$1") (pintype "passive"))
      (node (ref "C28") (pin "1") (pinfunction "1_1") (pintype "passive"))
      (node (ref "C5") (pin "P$1") (pinfunction "1_P$1") (pintype "passive"))
      (node (ref "C8") (pin "P$1") (pinfunction "1_P$1") (pintype "passive"))
      (node (ref "IC3") (pin "3") (pinfunction "OUT_3") (pintype "output"))
      (node (ref "R1") (pin "P$2") (pinfunction "2_P$2") (pintype "passive"))
      (node (ref "R12") (pin "P$2") (pinfunction "2_P$2") (pintype "passive"))
      (node (ref "R9") (pin "P$1") (pinfunction "1_P$1") (pintype "passive"))
      (node (ref "U$1") (pin "P$2") (pinfunction "5V_P$2") (pintype "power_in"))
      (node (ref "U$1") (pin "P$4") (pinfunction "5V_P$4") (pintype "power_in"))
      (node (ref "U2") (pin "4") (pinfunction "VIN_4") (pintype "input"))
    )
    (net (code "170") (name "VDD_1.2") (class "Default")
      (node (ref "C45") (pin "P$1") (pinfunction "1_P$1") (pintype "passive"))
      (node (ref "C46") (pin "P$1") (pinfunction "1_P$1") (pintype "passive"))
      (node (ref "U3") (pin "1") (pinfunction "VDD_1.2_1") (pintype "power_in"))
    )
    (net (code "171") (name "WARNOUT") (class "Default")
      (node (ref "U$2") (pin "P9") (pinfunction "WARNOUT_P9") (pintype "bidirectional"))
      (node (ref "U4") (pin "128") (pinfunction "P1_4_128") (pintype "bidirectional"))
    )
    (net (code "172") (name "XCIN") (class "Default")
      (node (ref "C50") (pin "P$1") (pinfunction "1_P$1") (pintype "passive"))
      (node (ref "U4") (pin "20") (pinfunction "XCIN_20") (pintype "bidirectional"))
      (node (ref "X3") (pin "P$1") (pinfunction "P$1_P$1") (pintype "bidirectional"))
    )
    (net (code "173") (name "XCOUT") (class "Default")
      (node (ref "C51") (pin "P$1") (pinfunction "1_P$1") (pintype "passive"))
      (node (ref "U4") (pin "21") (pinfunction "XCOUT_21") (pintype "bidirectional"))
      (node (ref "X3") (pin "P$2") (pinfunction "P$2_P$2") (pintype "bidirectional"))
    )
    (net (code "174") (name "XII") (class "Default")
      (node (ref "C42") (pin "P$1") (pinfunction "1_P$1") (pintype "passive"))
      (node (ref "U$3") (pin "1") (pinfunction "1_1") (pintype "bidirectional"))
      (node (ref "U3") (pin "8") (pinfunction "XI_8") (pintype "input"))
    )
    (net (code "175") (name "XOO") (class "Default")
      (node (ref "C41") (pin "P$1") (pinfunction "1_P$1") (pintype "passive"))
      (node (ref "U$3") (pin "3") (pinfunction "3_3") (pintype "bidirectional"))
      (node (ref "U3") (pin "7") (pinfunction "XO_7") (pintype "output"))
    )
    (net (code "176") (name "XTAL1") (class "Default")
      (node (ref "C52") (pin "P$1") (pinfunction "1_P$1") (pintype "passive"))
      (node (ref "U4") (pin "23") (pinfunction "P2_13/XTAL_23") (pintype "bidirectional"))
      (node (ref "X4") (pin "1") (pinfunction "1_1") (pintype "bidirectional"))
    )
    (net (code "177") (name "XTAL2") (class "Default")
      (node (ref "C53") (pin "P$1") (pinfunction "1_P$1") (pintype "passive"))
      (node (ref "U4") (pin "24") (pinfunction "P2_12/EXTAL_24") (pintype "bidirectional"))
      (node (ref "X4") (pin "3") (pinfunction "3_3") (pintype "bidirectional"))
    )
    (net (code "178") (name "ZX0") (class "Default")
      (node (ref "U$2") (pin "P2") (pinfunction "ZX0_P2") (pintype "bidirectional"))
      (node (ref "U4") (pin "135") (pinfunction "P8_2_135") (pintype "bidirectional"))
    )
    (net (code "179") (name "ZX1") (class "Default")
      (node (ref "U$2") (pin "P3") (pinfunction "ZX1_P3") (pintype "bidirectional"))
      (node (ref "U4") (pin "134") (pinfunction "P8_1_134") (pintype "bidirectional"))
    )
    (net (code "180") (name "ZX2") (class "Default")
      (node (ref "U$2") (pin "P4") (pinfunction "ZX2_P4") (pintype "bidirectional"))
      (node (ref "U4") (pin "133") (pinfunction "P8_0_133") (pintype "bidirectional"))
    )
    (net (code "181") (name "unconnected-(U4-VBAT-Pad18)") (class "Default")
      (node (ref "U4") (pin "18") (pinfunction "VBAT_18") (pintype "bidirectional"))
    )
    (net (code "182") (name "unconnected-(U5-NC1-PadP$1)") (class "Default")
      (node (ref "U5") (pin "P$1") (pinfunction "NC1_P$1") (pintype "bidirectional"))
    )
    (net (code "183") (name "unconnected-(U5-NC2-PadP$4)") (class "Default")
      (node (ref "U5") (pin "P$4") (pinfunction "NC2_P$4") (pintype "bidirectional"))
    )
    (net (code "184") (name "unconnected-(U5-NC3-PadP$7)") (class "Default")
      (node (ref "U5") (pin "P$7") (pinfunction "NC3_P$7") (pintype "bidirectional"))
    )
    (net (code "185") (name "unconnected-(U6-NC-Pad4)") (class "Default")
      (node (ref "U6") (pin "4") (pinfunction "NC_4") (pintype "no_connect"))
    )
    (net (code "186") (name "unconnected-(U7-NC-Pad4)") (class "Default")
      (node (ref "U7") (pin "4") (pinfunction "NC_4") (pintype "no_connect"))
    )
  )
)
